# veils_v40.net
KiCad netlist of a schematic drawn in EAGLE
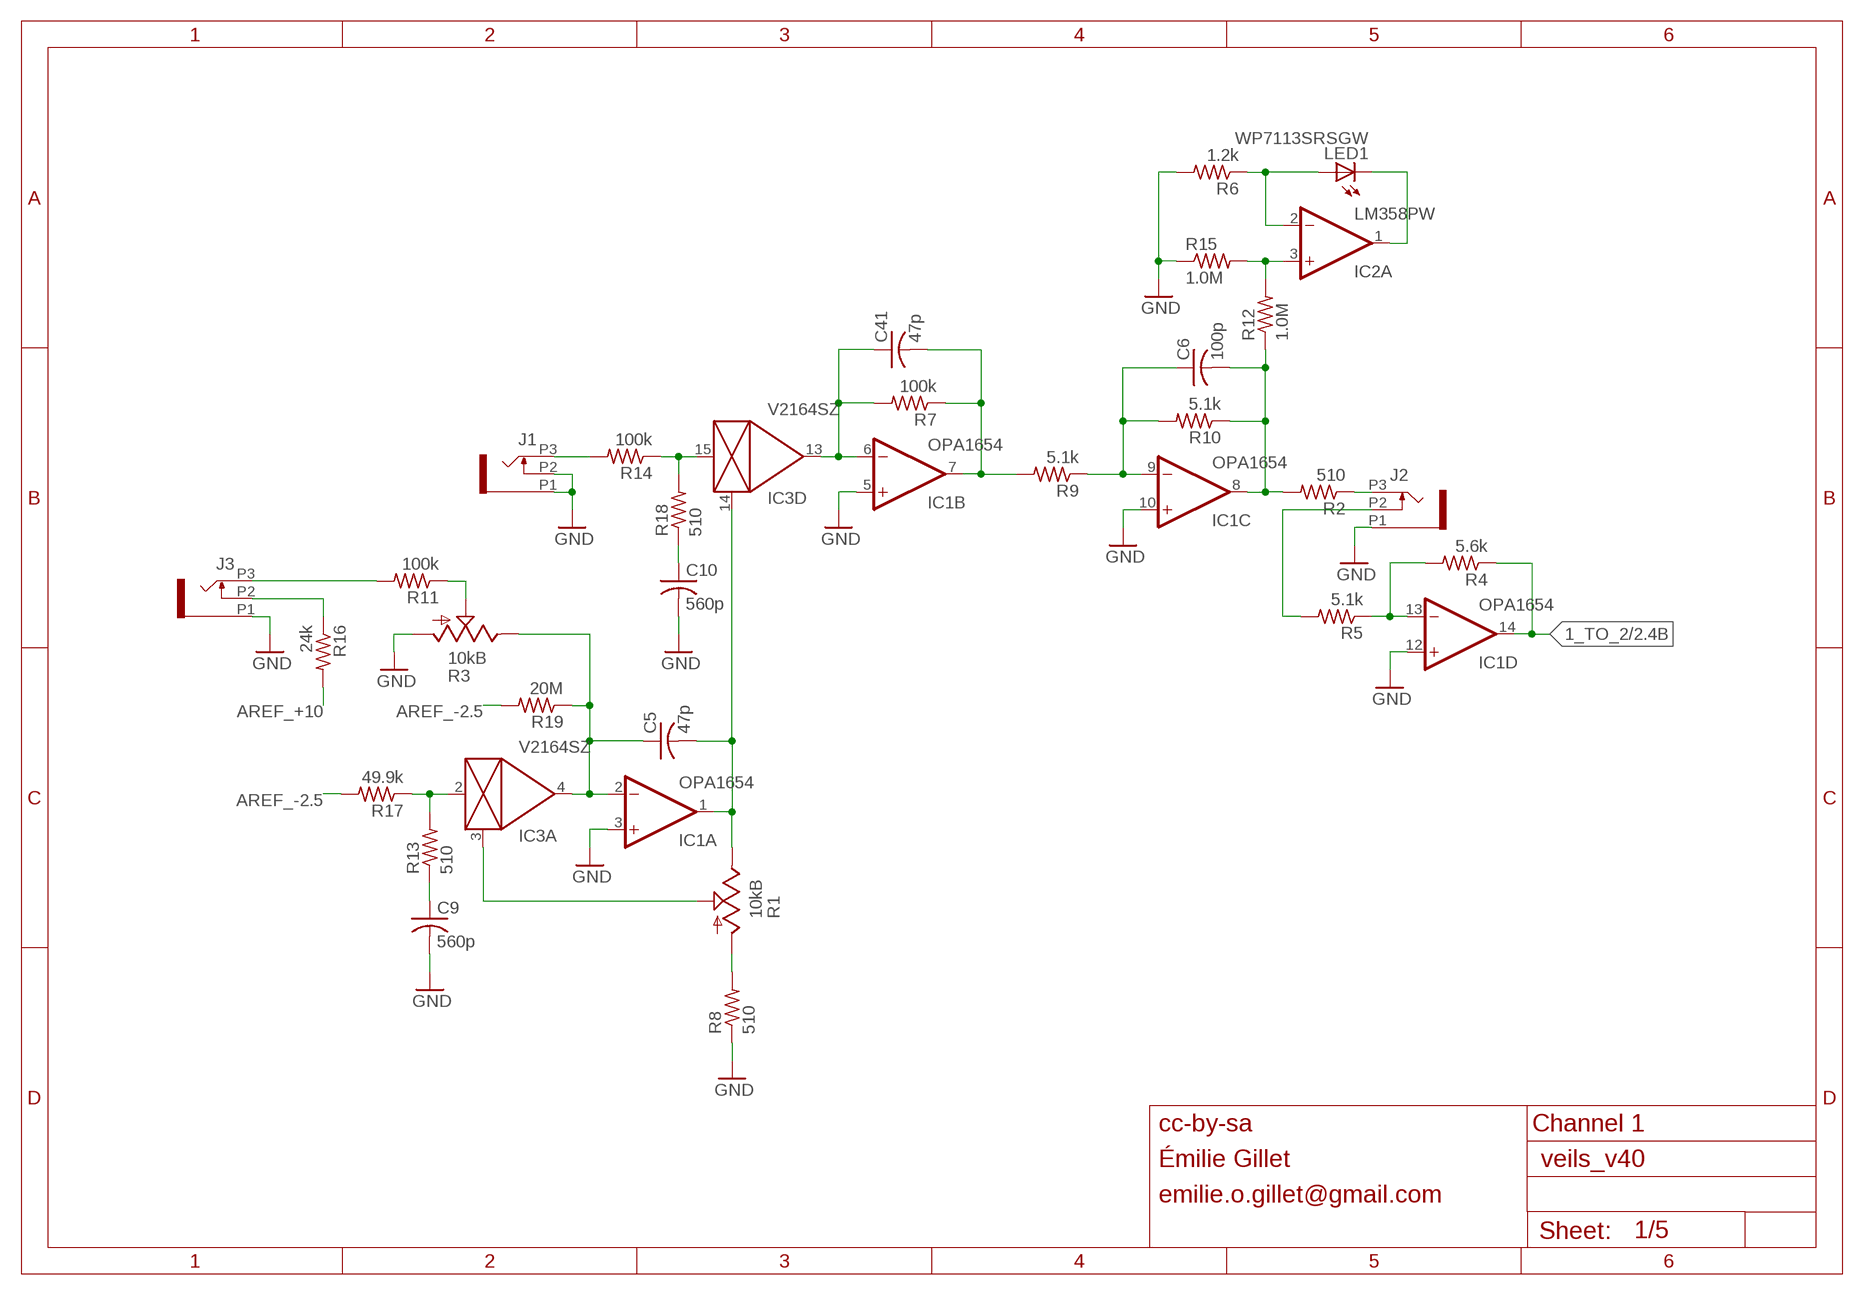
[diagram p0: schematic, sheet 1]
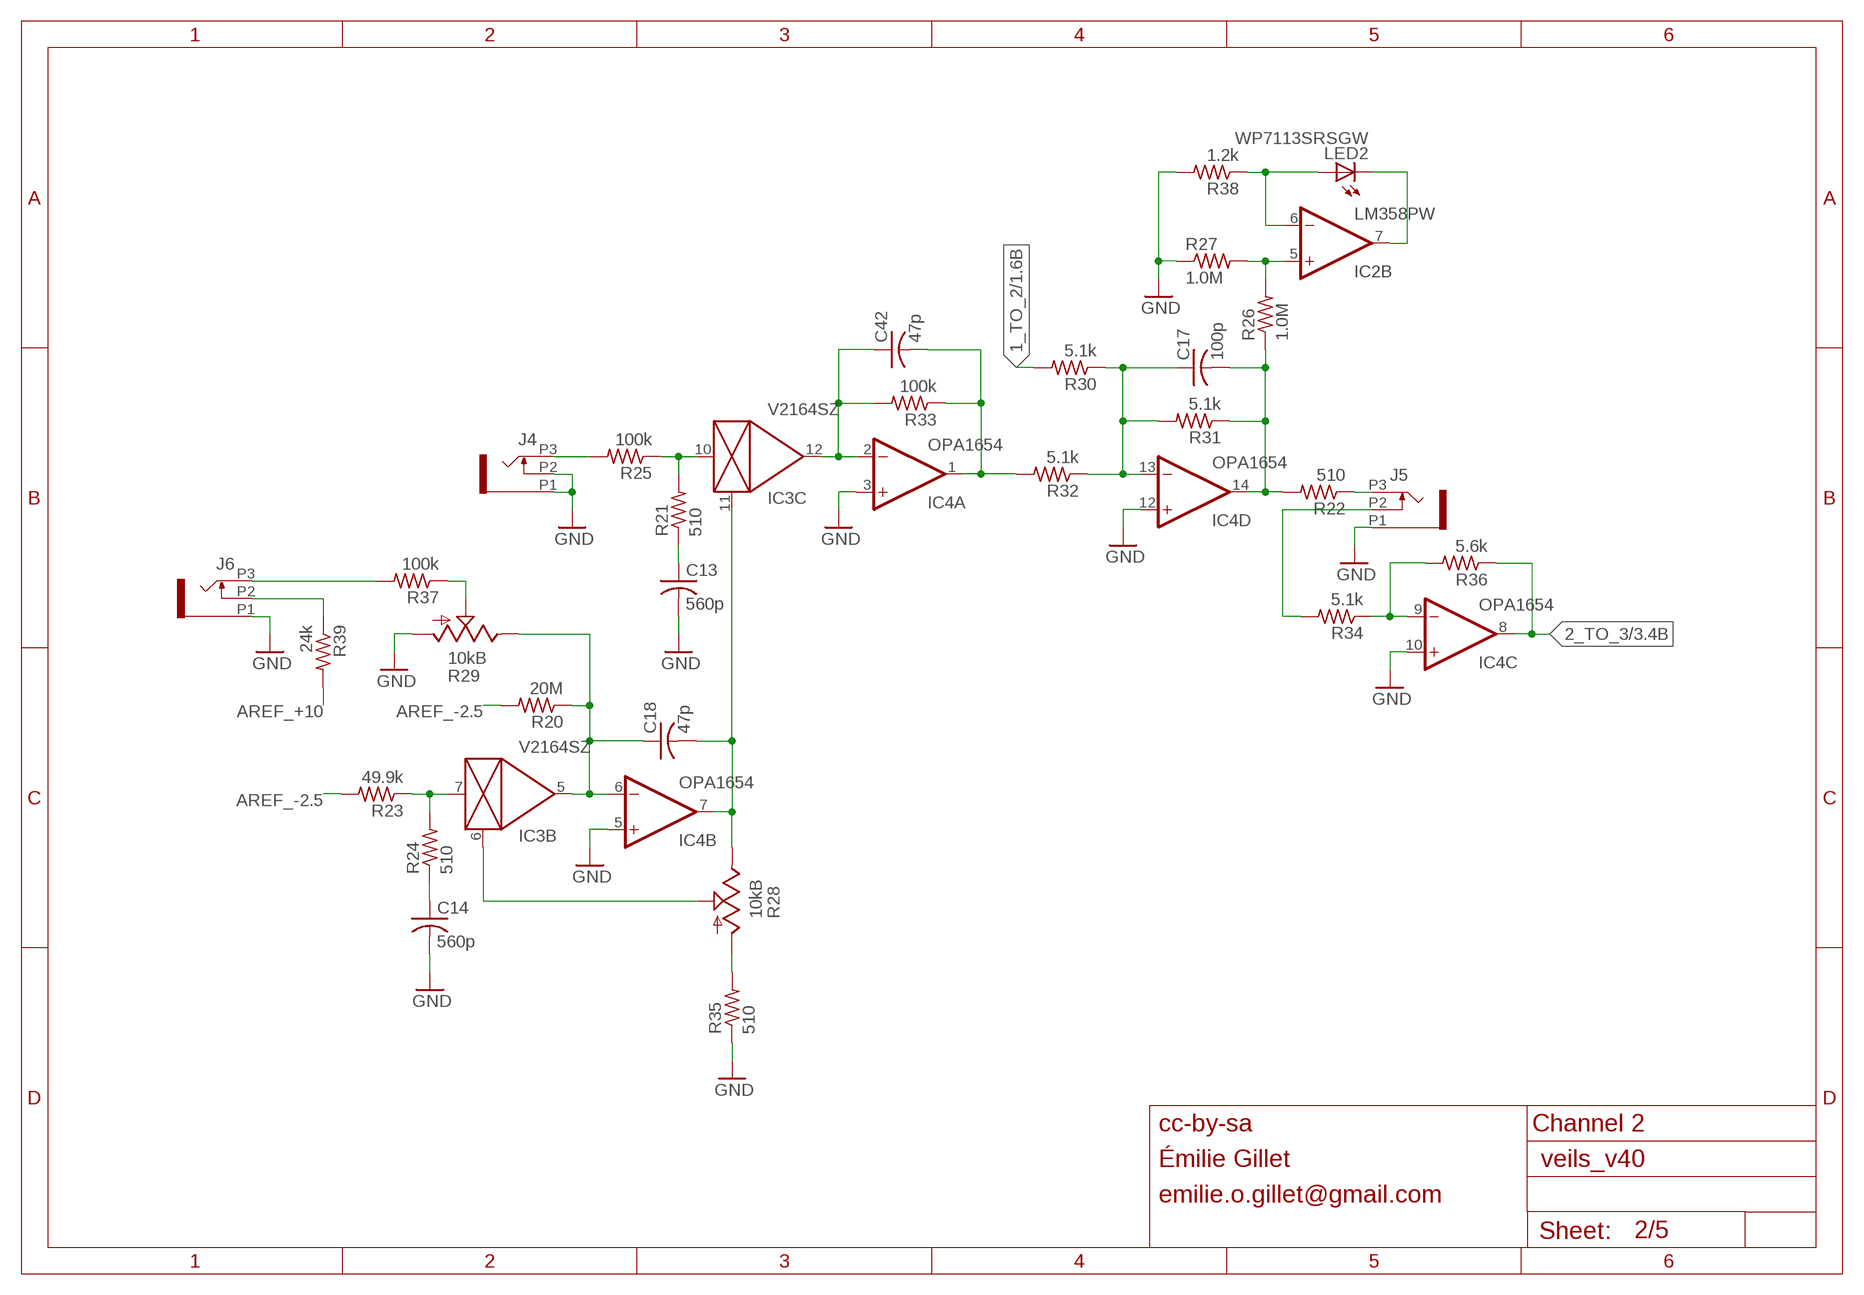
[diagram p1: schematic, sheet 2]
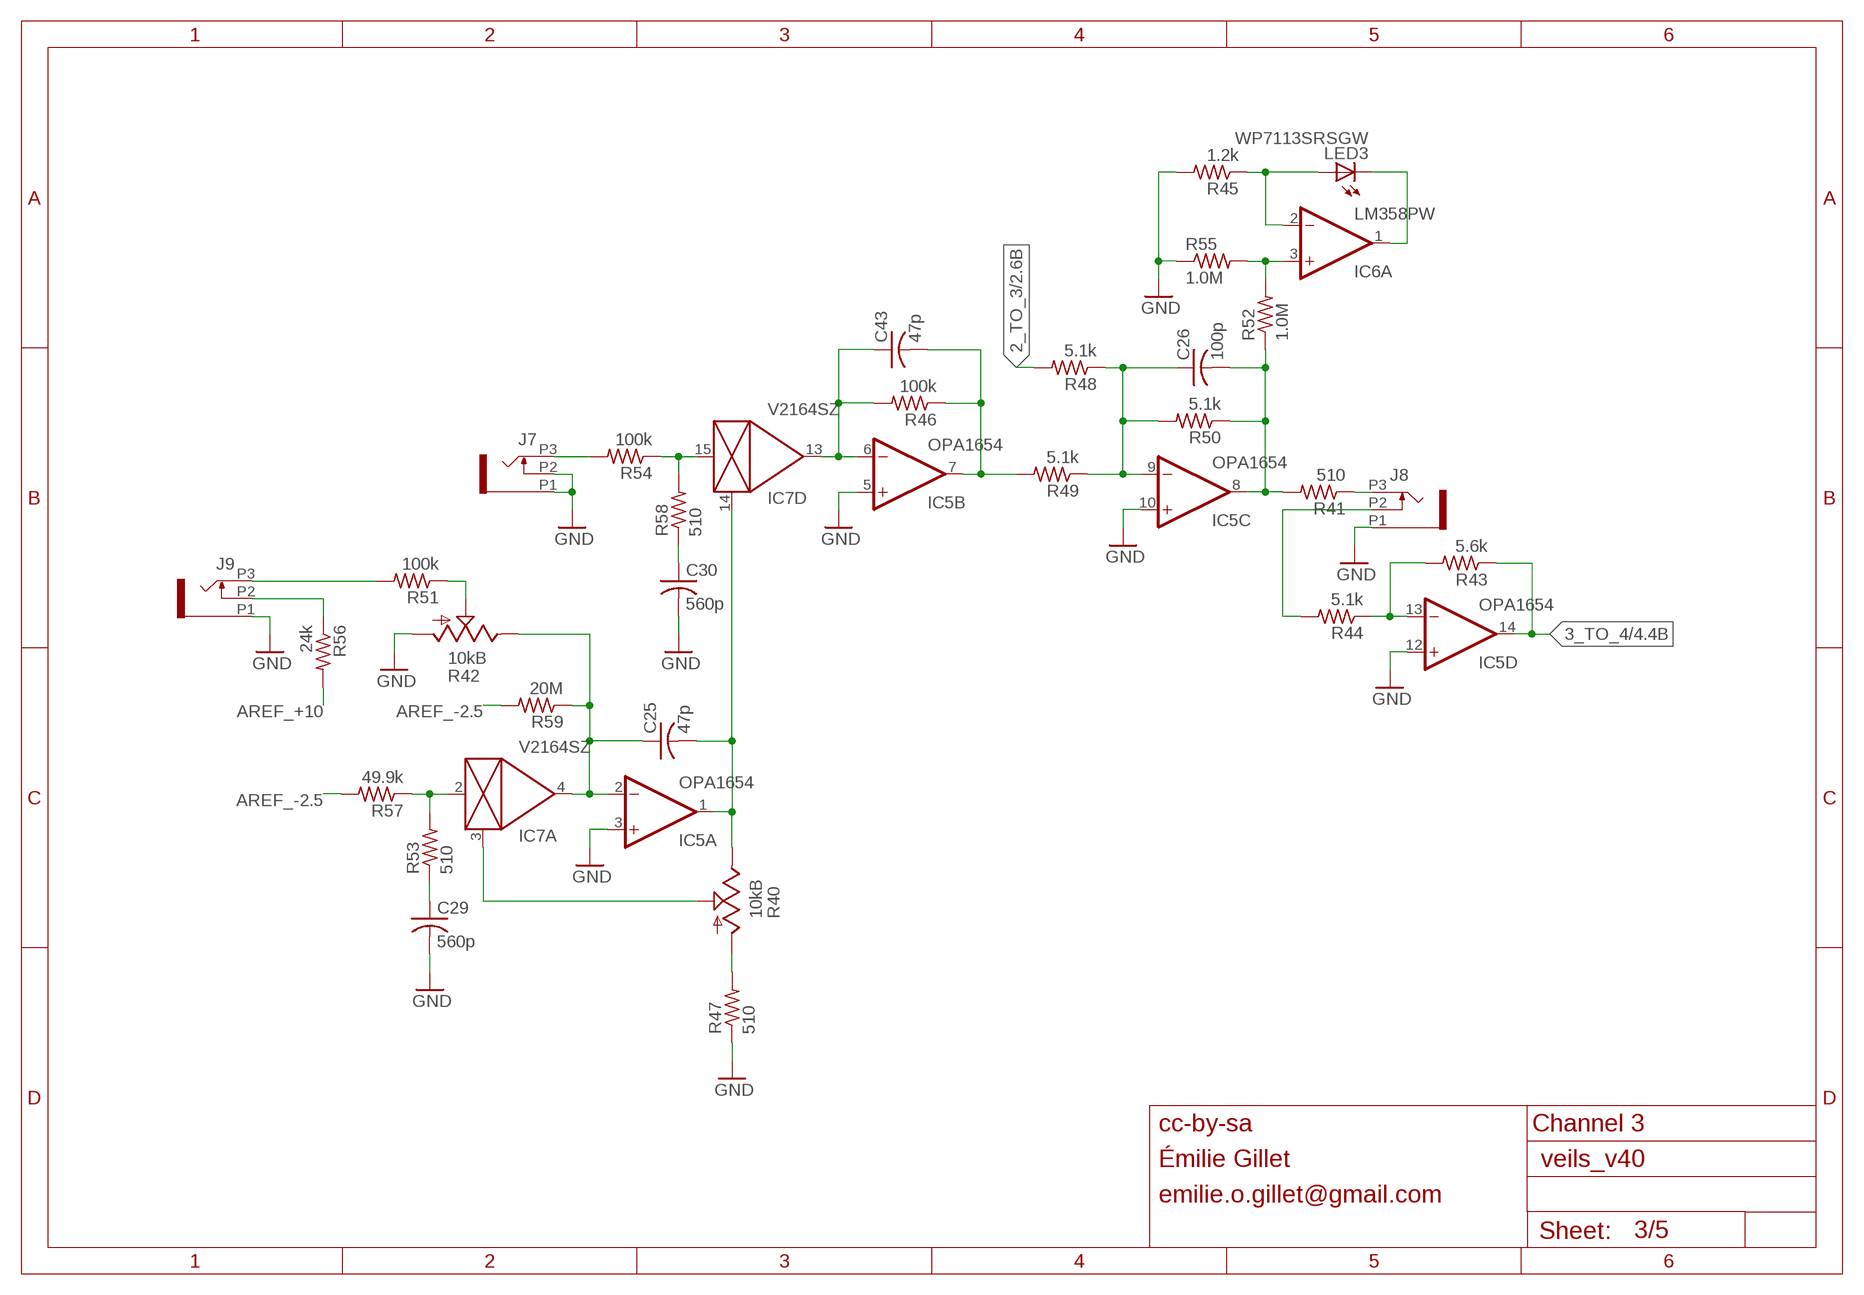
[diagram p2: schematic, sheet 3]
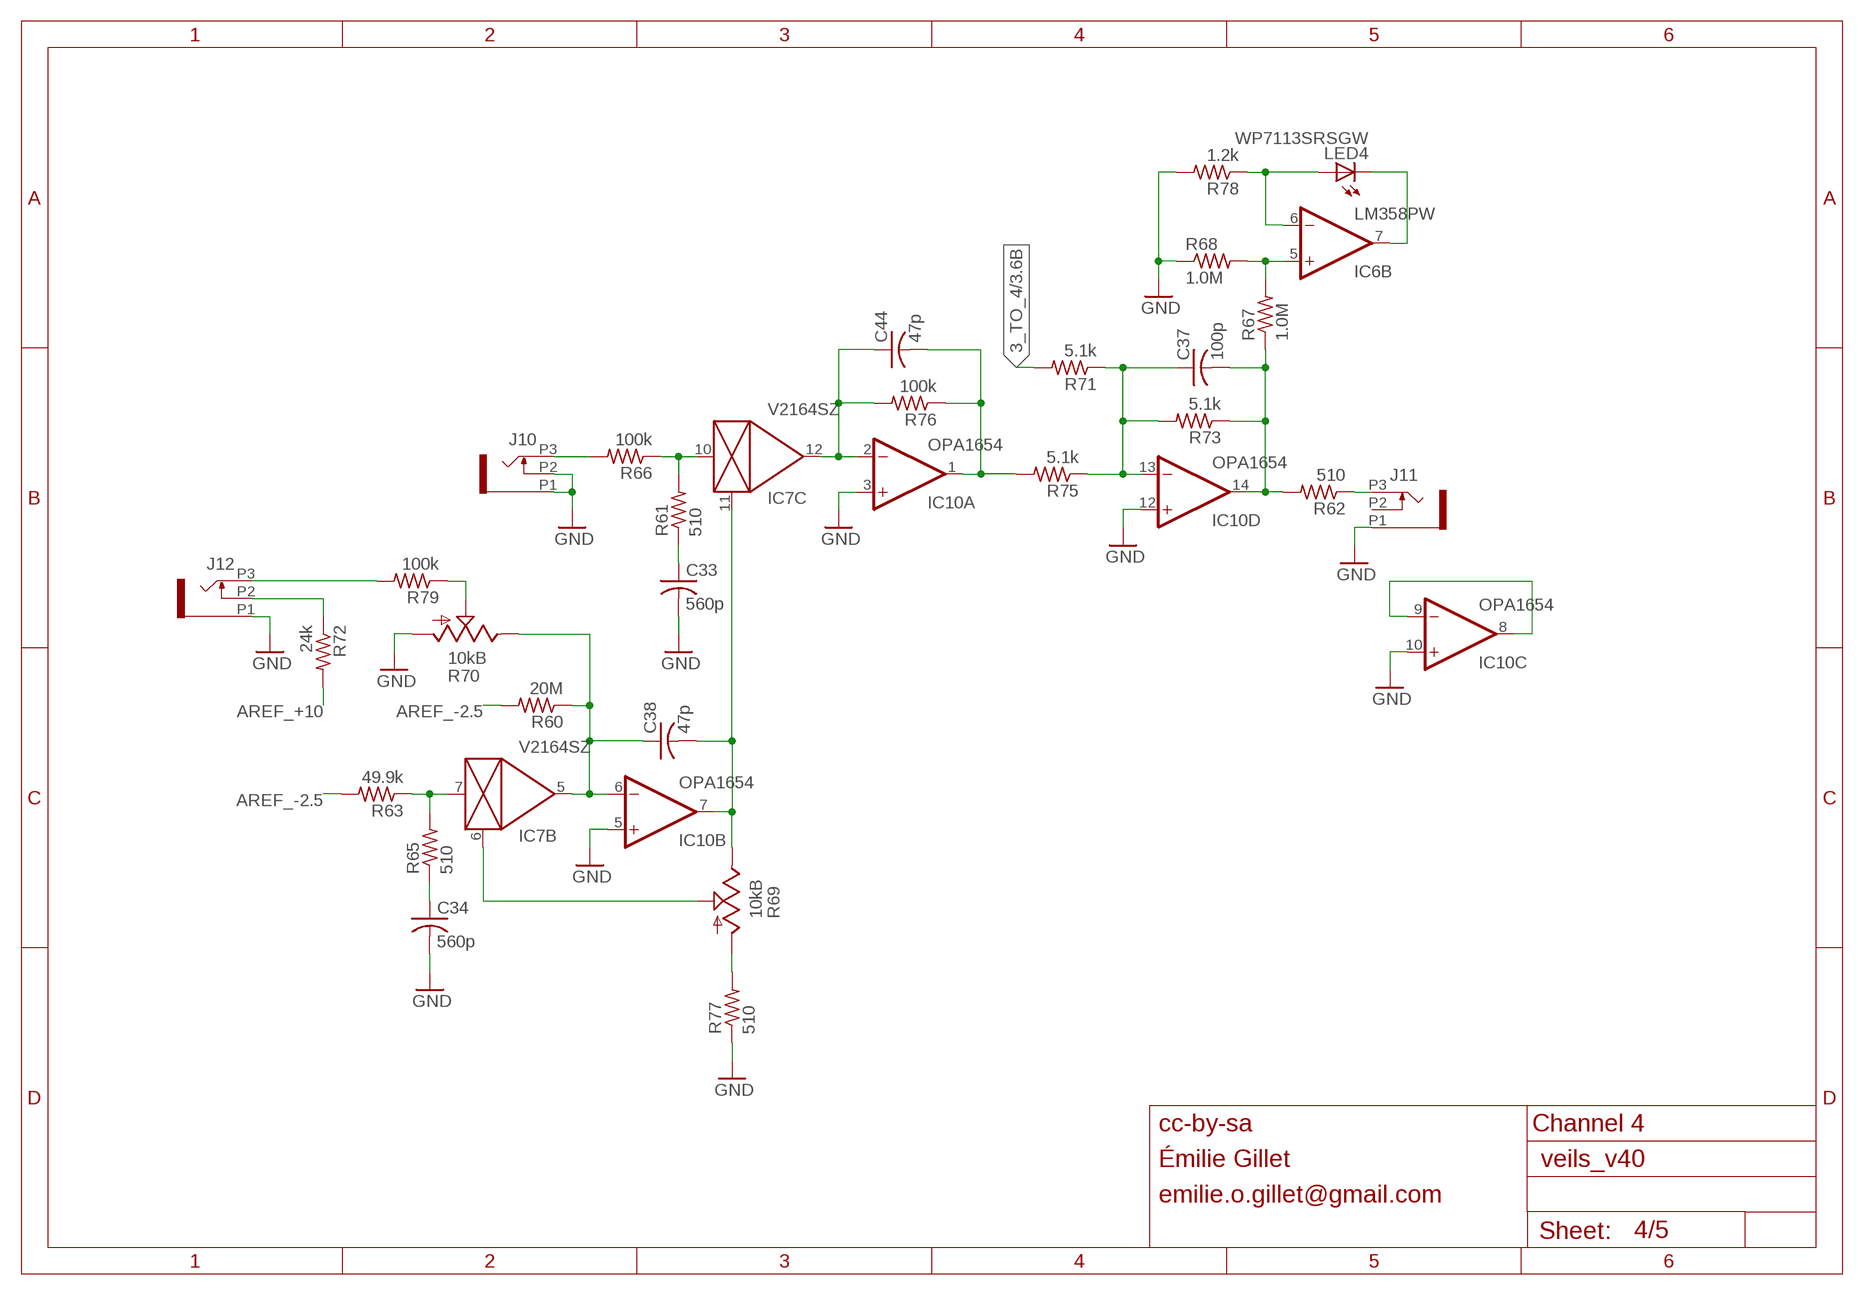
[diagram p3: schematic, sheet 4]
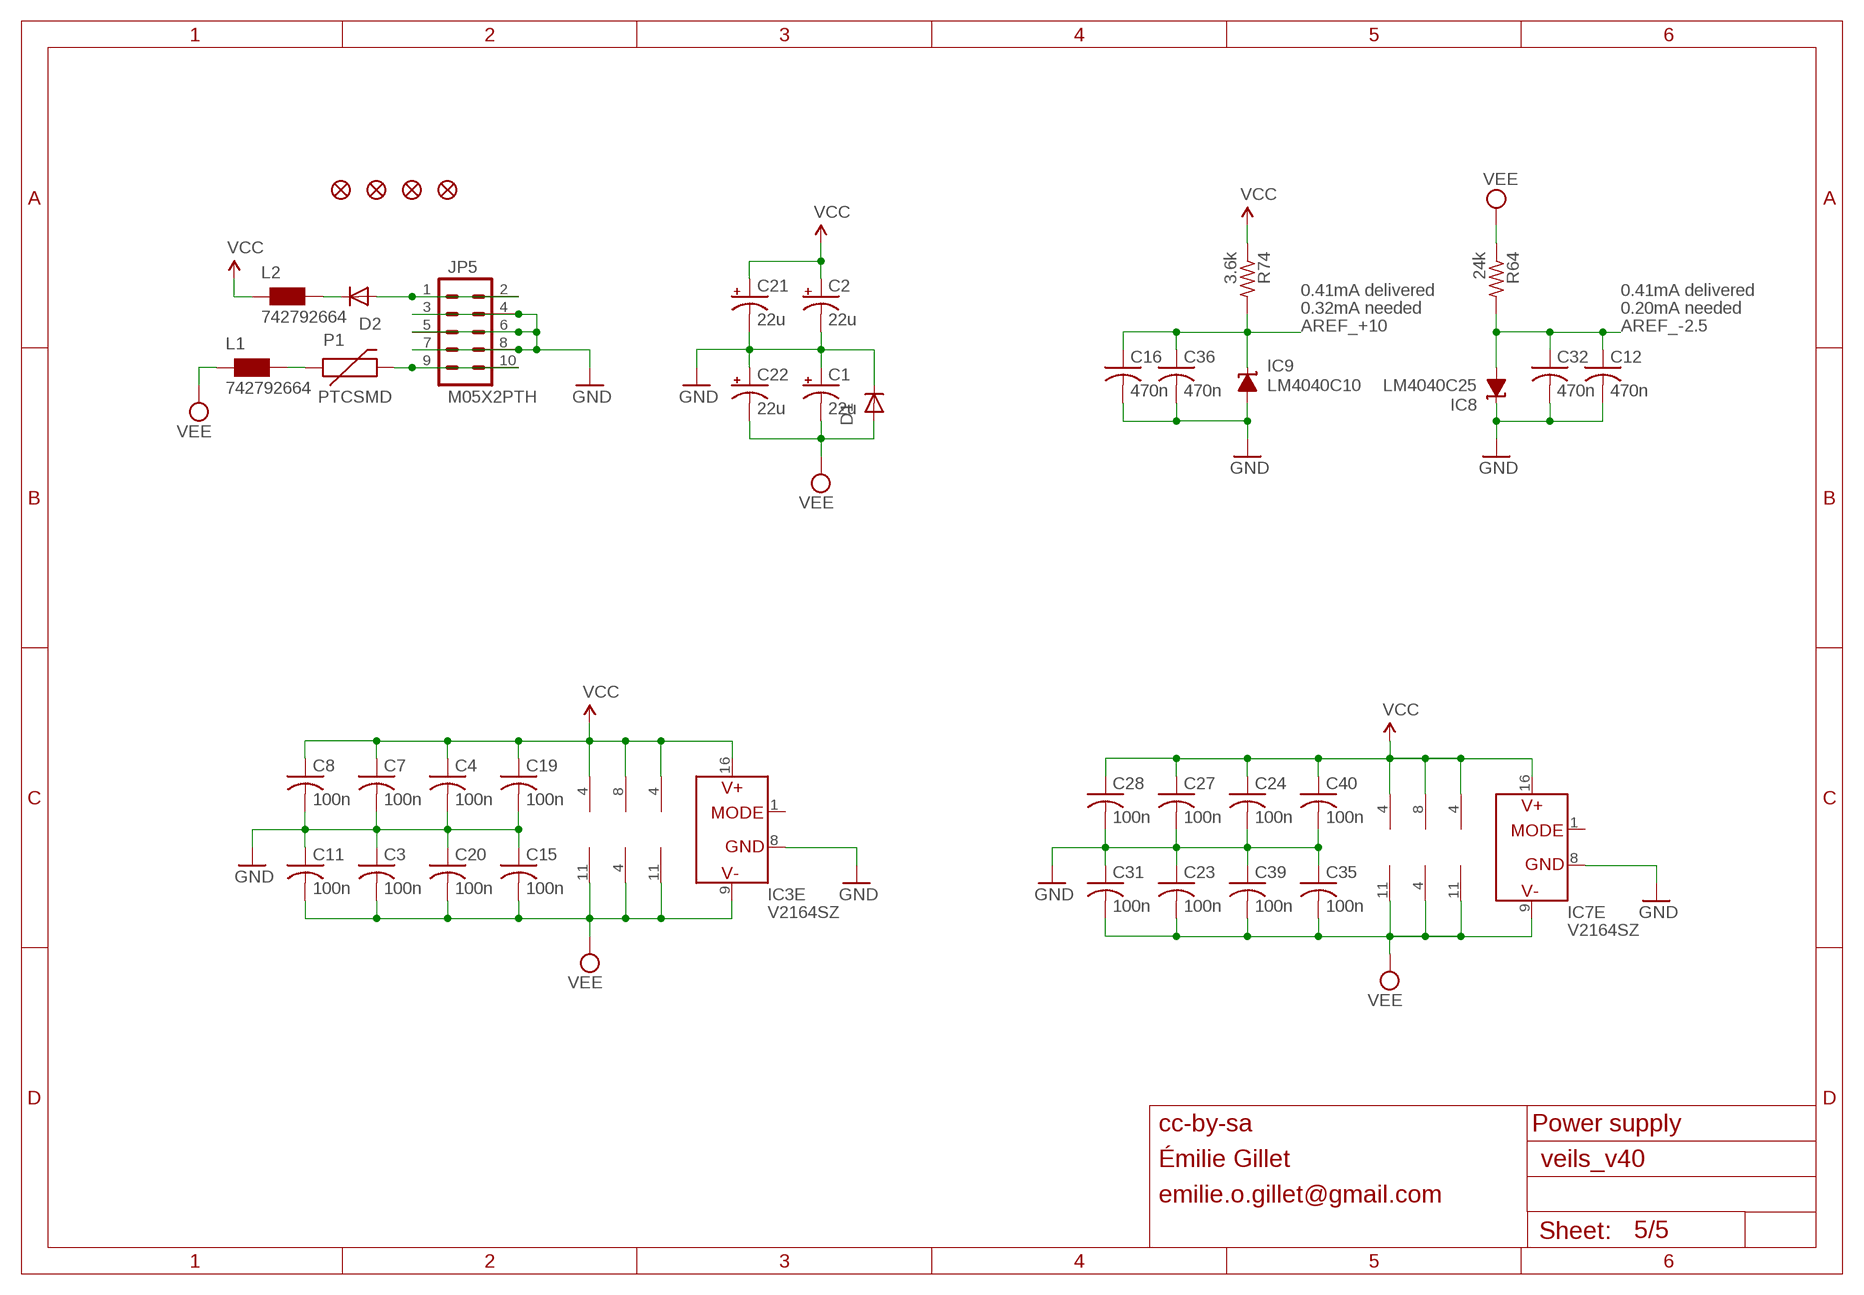
[diagram p4: schematic, sheet 5]

(export (version "E")
  (design (tool "Eeschema 10.0.6"))
  (components
    (comp (ref "C1")
      (value "22u")
      (footprint "eagle-import:PANASONIC_B")
      (libsource (lib "eagle-import") (part "CPOL-USB"))
    )
    (comp (ref "C2")
      (value "22u")
      (footprint "eagle-import:PANASONIC_B")
      (libsource (lib "eagle-import") (part "CPOL-USB"))
    )
    (comp (ref "C3")
      (value "100n")
      (footprint "eagle-import:C0402")
      (libsource (lib "eagle-import") (part "C-USC0402"))
    )
    (comp (ref "C4")
      (value "100n")
      (footprint "eagle-import:C0402")
      (libsource (lib "eagle-import") (part "C-USC0402"))
    )
    (comp (ref "C7")
      (value "100n")
      (footprint "eagle-import:C0402")
      (libsource (lib "eagle-import") (part "C-USC0402"))
    )
    (comp (ref "C8")
      (value "100n")
      (footprint "eagle-import:C0402")
      (libsource (lib "eagle-import") (part "C-USC0402"))
    )
    (comp (ref "C11")
      (value "100n")
      (footprint "eagle-import:C0402")
      (libsource (lib "eagle-import") (part "C-USC0402"))
    )
    (comp (ref "C12")
      (value "470n")
      (footprint "eagle-import:C0402")
      (libsource (lib "eagle-import") (part "C-USC0402"))
    )
    (comp (ref "C15")
      (value "100n")
      (footprint "eagle-import:C0402")
      (libsource (lib "eagle-import") (part "C-USC0402"))
    )
    (comp (ref "C16")
      (value "470n")
      (footprint "eagle-import:C0402")
      (libsource (lib "eagle-import") (part "C-USC0402"))
    )
    (comp (ref "C19")
      (value "100n")
      (footprint "eagle-import:C0402")
      (libsource (lib "eagle-import") (part "C-USC0402"))
    )
    (comp (ref "C20")
      (value "100n")
      (footprint "eagle-import:C0402")
      (libsource (lib "eagle-import") (part "C-USC0402"))
    )
    (comp (ref "C21")
      (value "22u")
      (footprint "eagle-import:PANASONIC_B")
      (libsource (lib "eagle-import") (part "CPOL-USB"))
    )
    (comp (ref "C22")
      (value "22u")
      (footprint "eagle-import:PANASONIC_B")
      (libsource (lib "eagle-import") (part "CPOL-USB"))
    )
    (comp (ref "C23")
      (value "100n")
      (footprint "eagle-import:C0402")
      (libsource (lib "eagle-import") (part "C-USC0402"))
    )
    (comp (ref "C24")
      (value "100n")
      (footprint "eagle-import:C0402")
      (libsource (lib "eagle-import") (part "C-USC0402"))
    )
    (comp (ref "C27")
      (value "100n")
      (footprint "eagle-import:C0402")
      (libsource (lib "eagle-import") (part "C-USC0402"))
    )
    (comp (ref "C28")
      (value "100n")
      (footprint "eagle-import:C0402")
      (libsource (lib "eagle-import") (part "C-USC0402"))
    )
    (comp (ref "C31")
      (value "100n")
      (footprint "eagle-import:C0402")
      (libsource (lib "eagle-import") (part "C-USC0402"))
    )
    (comp (ref "C32")
      (value "470n")
      (footprint "eagle-import:C0402")
      (libsource (lib "eagle-import") (part "C-USC0402"))
    )
    (comp (ref "C35")
      (value "100n")
      (footprint "eagle-import:C0402")
      (libsource (lib "eagle-import") (part "C-USC0402"))
    )
    (comp (ref "C36")
      (value "470n")
      (footprint "eagle-import:C0402")
      (libsource (lib "eagle-import") (part "C-USC0402"))
    )
    (comp (ref "C39")
      (value "100n")
      (footprint "eagle-import:C0402")
      (libsource (lib "eagle-import") (part "C-USC0402"))
    )
    (comp (ref "C40")
      (value "100n")
      (footprint "eagle-import:C0402")
      (libsource (lib "eagle-import") (part "C-USC0402"))
    )
    (comp (ref "D1")
      (value "1N5819HW")
      (footprint "eagle-import:SOD123")
      (libsource (lib "eagle-import") (part "DIODE-SOD123"))
    )
    (comp (ref "D2")
      (value "1N5819HW")
      (footprint "eagle-import:SOD123")
      (libsource (lib "eagle-import") (part "DIODE-SOD123"))
    )
    (comp (ref "IC1")
      (value "OPA1654")
      (footprint "eagle-import:TSSOP14")
      (libsource (lib "eagle-import") (part "TL074PW"))
    )
    (comp (ref "IC2")
      (value "LM358PW")
      (footprint "eagle-import:TSSOP8")
      (libsource (lib "eagle-import") (part "TL072PW"))
    )
    (comp (ref "IC3")
      (value "V2164SZ")
      (footprint "eagle-import:SOIC16N")
      (libsource (lib "eagle-import") (part "SSM2164S"))
    )
    (comp (ref "IC4")
      (value "OPA1654")
      (footprint "eagle-import:TSSOP14")
      (libsource (lib "eagle-import") (part "TL074PW"))
    )
    (comp (ref "IC5")
      (value "OPA1654")
      (footprint "eagle-import:TSSOP14")
      (libsource (lib "eagle-import") (part "TL074PW"))
    )
    (comp (ref "IC6")
      (value "LM358PW")
      (footprint "eagle-import:TSSOP8")
      (libsource (lib "eagle-import") (part "TL072PW"))
    )
    (comp (ref "IC7")
      (value "V2164SZ")
      (footprint "eagle-import:SOIC16N")
      (libsource (lib "eagle-import") (part "SSM2164S"))
    )
    (comp (ref "IC8")
      (value "LM4040C25")
      (footprint "eagle-import:DBZ_R-PDSO-G3")
      (libsource (lib "eagle-import") (part "LM4041DBZB12"))
    )
    (comp (ref "IC9")
      (value "LM4040C10")
      (footprint "eagle-import:DBZ_R-PDSO-G3")
      (libsource (lib "eagle-import") (part "LM4041DBZB12"))
    )
    (comp (ref "IC10")
      (value "OPA1654")
      (footprint "eagle-import:TSSOP14")
      (libsource (lib "eagle-import") (part "TL074PW"))
    )
    (comp (ref "JP1")
      (value "FIDUCIAL1X2")
      (footprint "eagle-import:FIDUCIAL-1X2")
      (libsource (lib "eagle-import") (part "FIDUCIAL1X2"))
    )
    (comp (ref "JP2")
      (value "FIDUCIAL1X2")
      (footprint "eagle-import:FIDUCIAL-1X2")
      (libsource (lib "eagle-import") (part "FIDUCIAL1X2"))
    )
    (comp (ref "JP3")
      (value "FIDUCIAL1X2")
      (footprint "eagle-import:FIDUCIAL-1X2")
      (libsource (lib "eagle-import") (part "FIDUCIAL1X2"))
    )
    (comp (ref "JP4")
      (value "FIDUCIAL1X2")
      (footprint "eagle-import:FIDUCIAL-1X2")
      (libsource (lib "eagle-import") (part "FIDUCIAL1X2"))
    )
    (comp (ref "JP5")
      (value "M05X2PTH")
      (footprint "eagle-import:AVR_ICSP")
      (libsource (lib "eagle-import") (part "M05X2PTH"))
    )
    (comp (ref "L1")
      (value "742792664")
      (footprint "eagle-import:0603")
      (libsource (lib "eagle-import") (part "WE-CBF_0603"))
    )
    (comp (ref "L2")
      (value "742792664")
      (footprint "eagle-import:0603")
      (libsource (lib "eagle-import") (part "WE-CBF_0603"))
    )
    (comp (ref "P1")
      (value "PTCSMD")
      (footprint "eagle-import:PTC-1206")
      (libsource (lib "eagle-import") (part "PTCSMD"))
    )
    (comp (ref "R64")
      (value "24k")
      (footprint "eagle-import:R0402")
      (libsource (lib "eagle-import") (part "R-US_R0402"))
    )
    (comp (ref "R74")
      (value "3.6k")
      (footprint "eagle-import:R0402")
      (libsource (lib "eagle-import") (part "R-US_R0402"))
    )
    (comp (ref "C13")
      (value "560p")
      (footprint "eagle-import:C0402")
      (libsource (lib "eagle-import") (part "C-USC0402"))
    )
    (comp (ref "C14")
      (value "560p")
      (footprint "eagle-import:C0402")
      (libsource (lib "eagle-import") (part "C-USC0402"))
    )
    (comp (ref "C17")
      (value "100p")
      (footprint "eagle-import:C0402")
      (libsource (lib "eagle-import") (part "C-USC0402"))
    )
    (comp (ref "C18")
      (value "47p")
      (footprint "eagle-import:C0402")
      (libsource (lib "eagle-import") (part "C-USC0402"))
    )
    (comp (ref "C42")
      (value "47p")
      (footprint "eagle-import:C0402")
      (libsource (lib "eagle-import") (part "C-USC0402"))
    )
    (comp (ref "J4")
      (value "PJ301_THONKICONN6")
      (footprint "eagle-import:WQP_PJ_301M6")
      (libsource (lib "eagle-import") (part "PJ301_THONKICONN6"))
    )
    (comp (ref "J5")
      (value "PJ301_THONKICONN6")
      (footprint "eagle-import:WQP_PJ_301M6")
      (libsource (lib "eagle-import") (part "PJ301_THONKICONN6"))
    )
    (comp (ref "J6")
      (value "PJ301_THONKICONN6")
      (footprint "eagle-import:WQP_PJ_301M6")
      (libsource (lib "eagle-import") (part "PJ301_THONKICONN6"))
    )
    (comp (ref "LED2")
      (value "WP7113SRSGW")
      (footprint "eagle-import:LED5MM")
      (libsource (lib "eagle-import") (part "LED5MM"))
    )
    (comp (ref "R20")
      (value "20M")
      (footprint "eagle-import:R0402")
      (libsource (lib "eagle-import") (part "R-US_R0402"))
    )
    (comp (ref "R21")
      (value "510")
      (footprint "eagle-import:R0402")
      (libsource (lib "eagle-import") (part "R-US_R0402"))
    )
    (comp (ref "R22")
      (value "510")
      (footprint "eagle-import:R0402")
      (libsource (lib "eagle-import") (part "R-US_R0402"))
    )
    (comp (ref "R23")
      (value "49.9k")
      (footprint "eagle-import:R0402")
      (libsource (lib "eagle-import") (part "R-US_R0402"))
    )
    (comp (ref "R24")
      (value "510")
      (footprint "eagle-import:R0402")
      (libsource (lib "eagle-import") (part "R-US_R0402"))
    )
    (comp (ref "R25")
      (value "100k")
      (footprint "eagle-import:R0402")
      (libsource (lib "eagle-import") (part "R-US_R0402"))
    )
    (comp (ref "R26")
      (value "1.0M")
      (footprint "eagle-import:R0402")
      (libsource (lib "eagle-import") (part "R-US_R0402"))
    )
    (comp (ref "R27")
      (value "1.0M")
      (footprint "eagle-import:R0402")
      (libsource (lib "eagle-import") (part "R-US_R0402"))
    )
    (comp (ref "R28")
      (value "10kB")
      (footprint "eagle-import:ALPS_POT_VERTICAL")
      (libsource (lib "eagle-import") (part "POT_USVERTICAL"))
    )
    (comp (ref "R29")
      (value "10kB")
      (footprint "eagle-import:ALPS_POT_VERTICAL_PS")
      (libsource (lib "eagle-import") (part "pot-alps_POT_USVERTICAL_PS"))
    )
    (comp (ref "R30")
      (value "5.1k")
      (footprint "eagle-import:R0402")
      (libsource (lib "eagle-import") (part "R-US_R0402"))
    )
    (comp (ref "R31")
      (value "5.1k")
      (footprint "eagle-import:R0402")
      (libsource (lib "eagle-import") (part "R-US_R0402"))
    )
    (comp (ref "R32")
      (value "5.1k")
      (footprint "eagle-import:R0402")
      (libsource (lib "eagle-import") (part "R-US_R0402"))
    )
    (comp (ref "R33")
      (value "100k")
      (footprint "eagle-import:R0402")
      (libsource (lib "eagle-import") (part "R-US_R0402"))
    )
    (comp (ref "R34")
      (value "5.1k")
      (footprint "eagle-import:R0402")
      (libsource (lib "eagle-import") (part "R-US_R0402"))
    )
    (comp (ref "R35")
      (value "510")
      (footprint "eagle-import:R0402")
      (libsource (lib "eagle-import") (part "R-US_R0402"))
    )
    (comp (ref "R36")
      (value "5.6k")
      (footprint "eagle-import:R0402")
      (libsource (lib "eagle-import") (part "R-US_R0402"))
    )
    (comp (ref "R37")
      (value "100k")
      (footprint "eagle-import:R0402")
      (libsource (lib "eagle-import") (part "R-US_R0402"))
    )
    (comp (ref "R38")
      (value "1.2k")
      (footprint "eagle-import:R0402")
      (libsource (lib "eagle-import") (part "R-US_R0402"))
    )
    (comp (ref "R39")
      (value "24k")
      (footprint "eagle-import:R0402")
      (libsource (lib "eagle-import") (part "R-US_R0402"))
    )
    (comp (ref "C33")
      (value "560p")
      (footprint "eagle-import:C0402")
      (libsource (lib "eagle-import") (part "C-USC0402"))
    )
    (comp (ref "C34")
      (value "560p")
      (footprint "eagle-import:C0402")
      (libsource (lib "eagle-import") (part "C-USC0402"))
    )
    (comp (ref "C37")
      (value "100p")
      (footprint "eagle-import:C0402")
      (libsource (lib "eagle-import") (part "C-USC0402"))
    )
    (comp (ref "C38")
      (value "47p")
      (footprint "eagle-import:C0402")
      (libsource (lib "eagle-import") (part "C-USC0402"))
    )
    (comp (ref "C44")
      (value "47p")
      (footprint "eagle-import:C0402")
      (libsource (lib "eagle-import") (part "C-USC0402"))
    )
    (comp (ref "J10")
      (value "PJ301_THONKICONN6")
      (footprint "eagle-import:WQP_PJ_301M6")
      (libsource (lib "eagle-import") (part "PJ301_THONKICONN6"))
    )
    (comp (ref "J11")
      (value "PJ301_THONKICONN6")
      (footprint "eagle-import:WQP_PJ_301M6")
      (libsource (lib "eagle-import") (part "PJ301_THONKICONN6"))
    )
    (comp (ref "J12")
      (value "PJ301_THONKICONN6")
      (footprint "eagle-import:WQP_PJ_301M6")
      (libsource (lib "eagle-import") (part "PJ301_THONKICONN6"))
    )
    (comp (ref "LED4")
      (value "WP7113SRSGW")
      (footprint "eagle-import:LED5MM")
      (libsource (lib "eagle-import") (part "LED5MM"))
    )
    (comp (ref "R60")
      (value "20M")
      (footprint "eagle-import:R0402")
      (libsource (lib "eagle-import") (part "R-US_R0402"))
    )
    (comp (ref "R61")
      (value "510")
      (footprint "eagle-import:R0402")
      (libsource (lib "eagle-import") (part "R-US_R0402"))
    )
    (comp (ref "R62")
      (value "510")
      (footprint "eagle-import:R0402")
      (libsource (lib "eagle-import") (part "R-US_R0402"))
    )
    (comp (ref "R63")
      (value "49.9k")
      (footprint "eagle-import:R0402")
      (libsource (lib "eagle-import") (part "R-US_R0402"))
    )
    (comp (ref "R65")
      (value "510")
      (footprint "eagle-import:R0402")
      (libsource (lib "eagle-import") (part "R-US_R0402"))
    )
    (comp (ref "R66")
      (value "100k")
      (footprint "eagle-import:R0402")
      (libsource (lib "eagle-import") (part "R-US_R0402"))
    )
    (comp (ref "R67")
      (value "1.0M")
      (footprint "eagle-import:R0402")
      (libsource (lib "eagle-import") (part "R-US_R0402"))
    )
    (comp (ref "R68")
      (value "1.0M")
      (footprint "eagle-import:R0402")
      (libsource (lib "eagle-import") (part "R-US_R0402"))
    )
    (comp (ref "R69")
      (value "10kB")
      (footprint "eagle-import:ALPS_POT_VERTICAL")
      (libsource (lib "eagle-import") (part "POT_USVERTICAL"))
    )
    (comp (ref "R70")
      (value "10kB")
      (footprint "eagle-import:ALPS_POT_VERTICAL_PS")
      (libsource (lib "eagle-import") (part "pot-alps_POT_USVERTICAL_PS"))
    )
    (comp (ref "R71")
      (value "5.1k")
      (footprint "eagle-import:R0402")
      (libsource (lib "eagle-import") (part "R-US_R0402"))
    )
    (comp (ref "R72")
      (value "24k")
      (footprint "eagle-import:R0402")
      (libsource (lib "eagle-import") (part "R-US_R0402"))
    )
    (comp (ref "R73")
      (value "5.1k")
      (footprint "eagle-import:R0402")
      (libsource (lib "eagle-import") (part "R-US_R0402"))
    )
    (comp (ref "R75")
      (value "5.1k")
      (footprint "eagle-import:R0402")
      (libsource (lib "eagle-import") (part "R-US_R0402"))
    )
    (comp (ref "R76")
      (value "100k")
      (footprint "eagle-import:R0402")
      (libsource (lib "eagle-import") (part "R-US_R0402"))
    )
    (comp (ref "R77")
      (value "510")
      (footprint "eagle-import:R0402")
      (libsource (lib "eagle-import") (part "R-US_R0402"))
    )
    (comp (ref "R78")
      (value "1.2k")
      (footprint "eagle-import:R0402")
      (libsource (lib "eagle-import") (part "R-US_R0402"))
    )
    (comp (ref "R79")
      (value "100k")
      (footprint "eagle-import:R0402")
      (libsource (lib "eagle-import") (part "R-US_R0402"))
    )
    (comp (ref "C25")
      (value "47p")
      (footprint "eagle-import:C0402")
      (libsource (lib "eagle-import") (part "C-USC0402"))
    )
    (comp (ref "C26")
      (value "100p")
      (footprint "eagle-import:C0402")
      (libsource (lib "eagle-import") (part "C-USC0402"))
    )
    (comp (ref "C29")
      (value "560p")
      (footprint "eagle-import:C0402")
      (libsource (lib "eagle-import") (part "C-USC0402"))
    )
    (comp (ref "C30")
      (value "560p")
      (footprint "eagle-import:C0402")
      (libsource (lib "eagle-import") (part "C-USC0402"))
    )
    (comp (ref "C43")
      (value "47p")
      (footprint "eagle-import:C0402")
      (libsource (lib "eagle-import") (part "C-USC0402"))
    )
    (comp (ref "J7")
      (value "PJ301_THONKICONN6")
      (footprint "eagle-import:WQP_PJ_301M6")
      (libsource (lib "eagle-import") (part "PJ301_THONKICONN6"))
    )
    (comp (ref "J8")
      (value "PJ301_THONKICONN6")
      (footprint "eagle-import:WQP_PJ_301M6")
      (libsource (lib "eagle-import") (part "PJ301_THONKICONN6"))
    )
    (comp (ref "J9")
      (value "PJ301_THONKICONN6")
      (footprint "eagle-import:WQP_PJ_301M6")
      (libsource (lib "eagle-import") (part "PJ301_THONKICONN6"))
    )
    (comp (ref "LED3")
      (value "WP7113SRSGW")
      (footprint "eagle-import:LED5MM")
      (libsource (lib "eagle-import") (part "LED5MM"))
    )
    (comp (ref "R40")
      (value "10kB")
      (footprint "eagle-import:ALPS_POT_VERTICAL")
      (libsource (lib "eagle-import") (part "POT_USVERTICAL"))
    )
    (comp (ref "R41")
      (value "510")
      (footprint "eagle-import:R0402")
      (libsource (lib "eagle-import") (part "R-US_R0402"))
    )
    (comp (ref "R42")
      (value "10kB")
      (footprint "eagle-import:ALPS_POT_VERTICAL_PS")
      (libsource (lib "eagle-import") (part "pot-alps_POT_USVERTICAL_PS"))
    )
    (comp (ref "R43")
      (value "5.6k")
      (footprint "eagle-import:R0402")
      (libsource (lib "eagle-import") (part "R-US_R0402"))
    )
    (comp (ref "R44")
      (value "5.1k")
      (footprint "eagle-import:R0402")
      (libsource (lib "eagle-import") (part "R-US_R0402"))
    )
    (comp (ref "R45")
      (value "1.2k")
      (footprint "eagle-import:R0402")
      (libsource (lib "eagle-import") (part "R-US_R0402"))
    )
    (comp (ref "R46")
      (value "100k")
      (footprint "eagle-import:R0402")
      (libsource (lib "eagle-import") (part "R-US_R0402"))
    )
    (comp (ref "R47")
      (value "510")
      (footprint "eagle-import:R0402")
      (libsource (lib "eagle-import") (part "R-US_R0402"))
    )
    (comp (ref "R48")
      (value "5.1k")
      (footprint "eagle-import:R0402")
      (libsource (lib "eagle-import") (part "R-US_R0402"))
    )
    (comp (ref "R49")
      (value "5.1k")
      (footprint "eagle-import:R0402")
      (libsource (lib "eagle-import") (part "R-US_R0402"))
    )
    (comp (ref "R50")
      (value "5.1k")
      (footprint "eagle-import:R0402")
      (libsource (lib "eagle-import") (part "R-US_R0402"))
    )
    (comp (ref "R51")
      (value "100k")
      (footprint "eagle-import:R0402")
      (libsource (lib "eagle-import") (part "R-US_R0402"))
    )
    (comp (ref "R52")
      (value "1.0M")
      (footprint "eagle-import:R0402")
      (libsource (lib "eagle-import") (part "R-US_R0402"))
    )
    (comp (ref "R53")
      (value "510")
      (footprint "eagle-import:R0402")
      (libsource (lib "eagle-import") (part "R-US_R0402"))
    )
    (comp (ref "R54")
      (value "100k")
      (footprint "eagle-import:R0402")
      (libsource (lib "eagle-import") (part "R-US_R0402"))
    )
    (comp (ref "R55")
      (value "1.0M")
      (footprint "eagle-import:R0402")
      (libsource (lib "eagle-import") (part "R-US_R0402"))
    )
    (comp (ref "R56")
      (value "24k")
      (footprint "eagle-import:R0402")
      (libsource (lib "eagle-import") (part "R-US_R0402"))
    )
    (comp (ref "R57")
      (value "49.9k")
      (footprint "eagle-import:R0402")
      (libsource (lib "eagle-import") (part "R-US_R0402"))
    )
    (comp (ref "R58")
      (value "510")
      (footprint "eagle-import:R0402")
      (libsource (lib "eagle-import") (part "R-US_R0402"))
    )
    (comp (ref "R59")
      (value "20M")
      (footprint "eagle-import:R0402")
      (libsource (lib "eagle-import") (part "R-US_R0402"))
    )
    (comp (ref "C5")
      (value "47p")
      (footprint "eagle-import:C0402")
      (libsource (lib "eagle-import") (part "C-USC0402"))
    )
    (comp (ref "C6")
      (value "100p")
      (footprint "eagle-import:C0402")
      (libsource (lib "eagle-import") (part "C-USC0402"))
    )
    (comp (ref "C9")
      (value "560p")
      (footprint "eagle-import:C0402")
      (libsource (lib "eagle-import") (part "C-USC0402"))
    )
    (comp (ref "C10")
      (value "560p")
      (footprint "eagle-import:C0402")
      (libsource (lib "eagle-import") (part "C-USC0402"))
    )
    (comp (ref "C41")
      (value "47p")
      (footprint "eagle-import:C0402")
      (libsource (lib "eagle-import") (part "C-USC0402"))
    )
    (comp (ref "J1")
      (value "PJ301_THONKICONN6")
      (footprint "eagle-import:WQP_PJ_301M6")
      (libsource (lib "eagle-import") (part "PJ301_THONKICONN6"))
    )
    (comp (ref "J2")
      (value "PJ301_THONKICONN6")
      (footprint "eagle-import:WQP_PJ_301M6")
      (libsource (lib "eagle-import") (part "PJ301_THONKICONN6"))
    )
    (comp (ref "J3")
      (value "PJ301_THONKICONN6")
      (footprint "eagle-import:WQP_PJ_301M6")
      (libsource (lib "eagle-import") (part "PJ301_THONKICONN6"))
    )
    (comp (ref "LED1")
      (value "WP7113SRSGW")
      (footprint "eagle-import:LED5MM")
      (libsource (lib "eagle-import") (part "LED5MM"))
    )
    (comp (ref "R1")
      (value "10kB")
      (footprint "eagle-import:ALPS_POT_VERTICAL")
      (libsource (lib "eagle-import") (part "POT_USVERTICAL"))
    )
    (comp (ref "R2")
      (value "510")
      (footprint "eagle-import:R0402")
      (libsource (lib "eagle-import") (part "R-US_R0402"))
    )
    (comp (ref "R3")
      (value "10kB")
      (footprint "eagle-import:ALPS_POT_VERTICAL_PS")
      (libsource (lib "eagle-import") (part "pot-alps_POT_USVERTICAL_PS"))
    )
    (comp (ref "R4")
      (value "5.6k")
      (footprint "eagle-import:R0402")
      (libsource (lib "eagle-import") (part "R-US_R0402"))
    )
    (comp (ref "R5")
      (value "5.1k")
      (footprint "eagle-import:R0402")
      (libsource (lib "eagle-import") (part "R-US_R0402"))
    )
    (comp (ref "R6")
      (value "1.2k")
      (footprint "eagle-import:R0402")
      (libsource (lib "eagle-import") (part "R-US_R0402"))
    )
    (comp (ref "R7")
      (value "100k")
      (footprint "eagle-import:R0402")
      (libsource (lib "eagle-import") (part "R-US_R0402"))
    )
    (comp (ref "R8")
      (value "510")
      (footprint "eagle-import:R0402")
      (libsource (lib "eagle-import") (part "R-US_R0402"))
    )
    (comp (ref "R9")
      (value "5.1k")
      (footprint "eagle-import:R0402")
      (libsource (lib "eagle-import") (part "R-US_R0402"))
    )
    (comp (ref "R10")
      (value "5.1k")
      (footprint "eagle-import:R0402")
      (libsource (lib "eagle-import") (part "R-US_R0402"))
    )
    (comp (ref "R11")
      (value "100k")
      (footprint "eagle-import:R0402")
      (libsource (lib "eagle-import") (part "R-US_R0402"))
    )
    (comp (ref "R12")
      (value "1.0M")
      (footprint "eagle-import:R0402")
      (libsource (lib "eagle-import") (part "R-US_R0402"))
    )
    (comp (ref "R13")
      (value "510")
      (footprint "eagle-import:R0402")
      (libsource (lib "eagle-import") (part "R-US_R0402"))
    )
    (comp (ref "R14")
      (value "100k")
      (footprint "eagle-import:R0402")
      (libsource (lib "eagle-import") (part "R-US_R0402"))
    )
    (comp (ref "R15")
      (value "1.0M")
      (footprint "eagle-import:R0402")
      (libsource (lib "eagle-import") (part "R-US_R0402"))
    )
    (comp (ref "R16")
      (value "24k")
      (footprint "eagle-import:R0402")
      (libsource (lib "eagle-import") (part "R-US_R0402"))
    )
    (comp (ref "R17")
      (value "49.9k")
      (footprint "eagle-import:R0402")
      (libsource (lib "eagle-import") (part "R-US_R0402"))
    )
    (comp (ref "R18")
      (value "510")
      (footprint "eagle-import:R0402")
      (libsource (lib "eagle-import") (part "R-US_R0402"))
    )
    (comp (ref "R19")
      (value "20M")
      (footprint "eagle-import:R0402")
      (libsource (lib "eagle-import") (part "R-US_R0402"))
    )
  )
  (nets
    (net (code "1") (name "1_TO_2") (class "Default")
      (node (ref "IC1") (pin "14") (pinfunction "OUT_14") (pintype "output"))
      (node (ref "R30") (pin "2") (pinfunction "2_2") (pintype "passive"))
      (node (ref "R4") (pin "1") (pinfunction "1_1") (pintype "passive"))
    )
    (net (code "2") (name "2_TO_3") (class "Default")
      (node (ref "IC4") (pin "8") (pinfunction "OUT_8") (pintype "output"))
      (node (ref "R36") (pin "1") (pinfunction "1_1") (pintype "passive"))
      (node (ref "R48") (pin "2") (pinfunction "2_2") (pintype "passive"))
    )
    (net (code "3") (name "3_TO_4") (class "Default")
      (node (ref "IC5") (pin "14") (pinfunction "OUT_14") (pintype "output"))
      (node (ref "R43") (pin "1") (pinfunction "1_1") (pintype "passive"))
      (node (ref "R71") (pin "2") (pinfunction "2_2") (pintype "passive"))
    )
    (net (code "4") (name "AREF_+10") (class "Default")
      (node (ref "C16") (pin "1") (pinfunction "1_1") (pintype "passive"))
      (node (ref "C36") (pin "1") (pinfunction "1_1") (pintype "passive"))
      (node (ref "IC9") (pin "1") (pinfunction "C_1") (pintype "passive"))
      (node (ref "R16") (pin "2") (pinfunction "2_2") (pintype "passive"))
      (node (ref "R39") (pin "2") (pinfunction "2_2") (pintype "passive"))
      (node (ref "R56") (pin "2") (pinfunction "2_2") (pintype "passive"))
      (node (ref "R72") (pin "2") (pinfunction "2_2") (pintype "passive"))
      (node (ref "R74") (pin "2") (pinfunction "2_2") (pintype "passive"))
    )
    (net (code "5") (name "AREF_-2.5") (class "Default")
      (node (ref "C12") (pin "1") (pinfunction "1_1") (pintype "passive"))
      (node (ref "C32") (pin "1") (pinfunction "1_1") (pintype "passive"))
      (node (ref "IC8") (pin "2") (pinfunction "A_2") (pintype "passive"))
      (node (ref "R17") (pin "2") (pinfunction "2_2") (pintype "passive"))
      (node (ref "R19") (pin "2") (pinfunction "2_2") (pintype "passive"))
      (node (ref "R20") (pin "2") (pinfunction "2_2") (pintype "passive"))
      (node (ref "R23") (pin "2") (pinfunction "2_2") (pintype "passive"))
      (node (ref "R57") (pin "2") (pinfunction "2_2") (pintype "passive"))
      (node (ref "R59") (pin "2") (pinfunction "2_2") (pintype "passive"))
      (node (ref "R60") (pin "2") (pinfunction "2_2") (pintype "passive"))
      (node (ref "R63") (pin "2") (pinfunction "2_2") (pintype "passive"))
      (node (ref "R64") (pin "2") (pinfunction "2_2") (pintype "passive"))
    )
    (net (code "6") (name "GND") (class "Default")
      (node (ref "C1") (pin "+") (pinfunction "+_+") (pintype "passive"))
      (node (ref "C10") (pin "2") (pinfunction "2_2") (pintype "passive"))
      (node (ref "C11") (pin "1") (pinfunction "1_1") (pintype "passive"))
      (node (ref "C12") (pin "2") (pinfunction "2_2") (pintype "passive"))
      (node (ref "C13") (pin "2") (pinfunction "2_2") (pintype "passive"))
      (node (ref "C14") (pin "2") (pinfunction "2_2") (pintype "passive"))
      (node (ref "C15") (pin "1") (pinfunction "1_1") (pintype "passive"))
      (node (ref "C16") (pin "2") (pinfunction "2_2") (pintype "passive"))
      (node (ref "C19") (pin "2") (pinfunction "2_2") (pintype "passive"))
      (node (ref "C2") (pin "-") (pinfunction "-_-") (pintype "passive"))
      (node (ref "C20") (pin "1") (pinfunction "1_1") (pintype "passive"))
      (node (ref "C21") (pin "-") (pinfunction "-_-") (pintype "passive"))
      (node (ref "C22") (pin "+") (pinfunction "+_+") (pintype "passive"))
      (node (ref "C23") (pin "1") (pinfunction "1_1") (pintype "passive"))
      (node (ref "C24") (pin "2") (pinfunction "2_2") (pintype "passive"))
      (node (ref "C27") (pin "2") (pinfunction "2_2") (pintype "passive"))
      (node (ref "C28") (pin "2") (pinfunction "2_2") (pintype "passive"))
      (node (ref "C29") (pin "2") (pinfunction "2_2") (pintype "passive"))
      (node (ref "C3") (pin "1") (pinfunction "1_1") (pintype "passive"))
      (node (ref "C30") (pin "2") (pinfunction "2_2") (pintype "passive"))
      (node (ref "C31") (pin "1") (pinfunction "1_1") (pintype "passive"))
      (node (ref "C32") (pin "2") (pinfunction "2_2") (pintype "passive"))
      (node (ref "C33") (pin "2") (pinfunction "2_2") (pintype "passive"))
      (node (ref "C34") (pin "2") (pinfunction "2_2") (pintype "passive"))
      (node (ref "C35") (pin "1") (pinfunction "1_1") (pintype "passive"))
      (node (ref "C36") (pin "2") (pinfunction "2_2") (pintype "passive"))
      (node (ref "C39") (pin "1") (pinfunction "1_1") (pintype "passive"))
      (node (ref "C4") (pin "2") (pinfunction "2_2") (pintype "passive"))
      (node (ref "C40") (pin "2") (pinfunction "2_2") (pintype "passive"))
      (node (ref "C7") (pin "2") (pinfunction "2_2") (pintype "passive"))
      (node (ref "C8") (pin "2") (pinfunction "2_2") (pintype "passive"))
      (node (ref "C9") (pin "2") (pinfunction "2_2") (pintype "passive"))
      (node (ref "D1") (pin "C") (pinfunction "C_C") (pintype "passive"))
      (node (ref "IC1") (pin "10") (pinfunction "+IN_10") (pintype "input"))
      (node (ref "IC1") (pin "12") (pinfunction "+IN_12") (pintype "input"))
      (node (ref "IC1") (pin "3") (pinfunction "+IN_3") (pintype "input"))
      (node (ref "IC1") (pin "5") (pinfunction "+IN_5") (pintype "input"))
      (node (ref "IC10") (pin "10") (pinfunction "+IN_10") (pintype "input"))
      (node (ref "IC10") (pin "12") (pinfunction "+IN_12") (pintype "input"))
      (node (ref "IC10") (pin "3") (pinfunction "+IN_3") (pintype "input"))
      (node (ref "IC10") (pin "5") (pinfunction "+IN_5") (pintype "input"))
      (node (ref "IC3") (pin "8") (pinfunction "GND_8") (pintype "power_in"))
      (node (ref "IC4") (pin "10") (pinfunction "+IN_10") (pintype "input"))
      (node (ref "IC4") (pin "12") (pinfunction "+IN_12") (pintype "input"))
      (node (ref "IC4") (pin "3") (pinfunction "+IN_3") (pintype "input"))
      (node (ref "IC4") (pin "5") (pinfunction "+IN_5") (pintype "input"))
      (node (ref "IC5") (pin "10") (pinfunction "+IN_10") (pintype "input"))
      (node (ref "IC5") (pin "12") (pinfunction "+IN_12") (pintype "input"))
      (node (ref "IC5") (pin "3") (pinfunction "+IN_3") (pintype "input"))
      (node (ref "IC5") (pin "5") (pinfunction "+IN_5") (pintype "input"))
      (node (ref "IC7") (pin "8") (pinfunction "GND_8") (pintype "power_in"))
      (node (ref "IC8") (pin "1") (pinfunction "C_1") (pintype "passive"))
      (node (ref "IC9") (pin "2") (pinfunction "A_2") (pintype "passive"))
      (node (ref "J1") (pin "P1") (pinfunction "1_P1") (pintype "passive"))
      (node (ref "J1") (pin "P2") (pinfunction "2_P2") (pintype "passive"))
      (node (ref "J10") (pin "P1") (pinfunction "1_P1") (pintype "passive"))
      (node (ref "J10") (pin "P2") (pinfunction "2_P2") (pintype "passive"))
      (node (ref "J11") (pin "P1") (pinfunction "1_P1") (pintype "passive"))
      (node (ref "J12") (pin "P1") (pinfunction "1_P1") (pintype "passive"))
      (node (ref "J2") (pin "P1") (pinfunction "1_P1") (pintype "passive"))
      (node (ref "J3") (pin "P1") (pinfunction "1_P1") (pintype "passive"))
      (node (ref "J4") (pin "P1") (pinfunction "1_P1") (pintype "passive"))
      (node (ref "J4") (pin "P2") (pinfunction "2_P2") (pintype "passive"))
      (node (ref "J5") (pin "P1") (pinfunction "1_P1") (pintype "passive"))
      (node (ref "J6") (pin "P1") (pinfunction "1_P1") (pintype "passive"))
      (node (ref "J7") (pin "P1") (pinfunction "1_P1") (pintype "passive"))
      (node (ref "J7") (pin "P2") (pinfunction "2_P2") (pintype "passive"))
      (node (ref "J8") (pin "P1") (pinfunction "1_P1") (pintype "passive"))
      (node (ref "J9") (pin "P1") (pinfunction "1_P1") (pintype "passive"))
      (node (ref "JP5") (pin "3") (pinfunction "3_3") (pintype "passive"))
      (node (ref "JP5") (pin "4") (pinfunction "4_4") (pintype "passive"))
      (node (ref "JP5") (pin "5") (pinfunction "5_5") (pintype "passive"))
      (node (ref "JP5") (pin "6") (pinfunction "6_6") (pintype "passive"))
      (node (ref "JP5") (pin "7") (pinfunction "7_7") (pintype "passive"))
      (node (ref "JP5") (pin "8") (pinfunction "8_8") (pintype "passive"))
      (node (ref "R15") (pin "1") (pinfunction "1_1") (pintype "passive"))
      (node (ref "R27") (pin "1") (pinfunction "1_1") (pintype "passive"))
      (node (ref "R29") (pin "P$3") (pinfunction "A_P$3") (pintype "passive"))
      (node (ref "R3") (pin "P$3") (pinfunction "A_P$3") (pintype "passive"))
      (node (ref "R35") (pin "1") (pinfunction "1_1") (pintype "passive"))
      (node (ref "R38") (pin "2") (pinfunction "2_2") (pintype "passive"))
      (node (ref "R42") (pin "P$3") (pinfunction "A_P$3") (pintype "passive"))
      (node (ref "R45") (pin "2") (pinfunction "2_2") (pintype "passive"))
      (node (ref "R47") (pin "1") (pinfunction "1_1") (pintype "passive"))
      (node (ref "R55") (pin "1") (pinfunction "1_1") (pintype "passive"))
      (node (ref "R6") (pin "2") (pinfunction "2_2") (pintype "passive"))
      (node (ref "R68") (pin "1") (pinfunction "1_1") (pintype "passive"))
      (node (ref "R70") (pin "P$3") (pinfunction "A_P$3") (pintype "passive"))
      (node (ref "R77") (pin "1") (pinfunction "1_1") (pintype "passive"))
      (node (ref "R78") (pin "2") (pinfunction "2_2") (pintype "passive"))
      (node (ref "R8") (pin "1") (pinfunction "1_1") (pintype "passive"))
    )
    (net (code "7") (name "Net-(C9-Pad1)") (class "Default")
      (node (ref "C9") (pin "1") (pinfunction "1_1") (pintype "passive"))
      (node (ref "R13") (pin "1") (pinfunction "1_1") (pintype "passive"))
    )
    (net (code "8") (name "Net-(C10-Pad1)") (class "Default")
      (node (ref "C10") (pin "1") (pinfunction "1_1") (pintype "passive"))
      (node (ref "R18") (pin "1") (pinfunction "1_1") (pintype "passive"))
    )
    (net (code "9") (name "Net-(C13-Pad1)") (class "Default")
      (node (ref "C13") (pin "1") (pinfunction "1_1") (pintype "passive"))
      (node (ref "R21") (pin "1") (pinfunction "1_1") (pintype "passive"))
    )
    (net (code "10") (name "Net-(C14-Pad1)") (class "Default")
      (node (ref "C14") (pin "1") (pinfunction "1_1") (pintype "passive"))
      (node (ref "R24") (pin "1") (pinfunction "1_1") (pintype "passive"))
    )
    (net (code "11") (name "Net-(C29-Pad1)") (class "Default")
      (node (ref "C29") (pin "1") (pinfunction "1_1") (pintype "passive"))
      (node (ref "R53") (pin "1") (pinfunction "1_1") (pintype "passive"))
    )
    (net (code "12") (name "Net-(C30-Pad1)") (class "Default")
      (node (ref "C30") (pin "1") (pinfunction "1_1") (pintype "passive"))
      (node (ref "R58") (pin "1") (pinfunction "1_1") (pintype "passive"))
    )
    (net (code "13") (name "Net-(C33-Pad1)") (class "Default")
      (node (ref "C33") (pin "1") (pinfunction "1_1") (pintype "passive"))
      (node (ref "R61") (pin "1") (pinfunction "1_1") (pintype "passive"))
    )
    (net (code "14") (name "Net-(C34-Pad1)") (class "Default")
      (node (ref "C34") (pin "1") (pinfunction "1_1") (pintype "passive"))
      (node (ref "R65") (pin "1") (pinfunction "1_1") (pintype "passive"))
    )
    (net (code "15") (name "Net-(D2-PadA)") (class "Default")
      (node (ref "D2") (pin "A") (pinfunction "A_A") (pintype "passive"))
      (node (ref "JP5") (pin "1") (pinfunction "1_1") (pintype "passive"))
      (node (ref "JP5") (pin "2") (pinfunction "2_2") (pintype "passive"))
    )
    (net (code "16") (name "Net-(D2-PadC)") (class "Default")
      (node (ref "D2") (pin "C") (pinfunction "C_C") (pintype "passive"))
      (node (ref "L2") (pin "2") (pinfunction "2_2") (pintype "passive"))
    )
    (net (code "17") (name "Net-(IC1A--IN)") (class "Default")
      (node (ref "C5") (pin "1") (pinfunction "1_1") (pintype "passive"))
      (node (ref "IC1") (pin "2") (pinfunction "-IN_2") (pintype "input"))
      (node (ref "IC3") (pin "4") (pinfunction "OUT_4") (pintype "output"))
      (node (ref "R19") (pin "1") (pinfunction "1_1") (pintype "passive"))
      (node (ref "R3") (pin "P$1") (pinfunction "E_P$1") (pintype "passive"))
    )
    (net (code "18") (name "Net-(IC1A-OUT)") (class "Default")
      (node (ref "C5") (pin "2") (pinfunction "2_2") (pintype "passive"))
      (node (ref "IC1") (pin "1") (pinfunction "OUT_1") (pintype "output"))
      (node (ref "IC3") (pin "14") (pinfunction "CTRL_14") (pintype "input"))
      (node (ref "R1") (pin "P$1") (pinfunction "E_P$1") (pintype "passive"))
    )
    (net (code "19") (name "Net-(IC1B--IN)") (class "Default")
      (node (ref "C41") (pin "1") (pinfunction "1_1") (pintype "passive"))
      (node (ref "IC1") (pin "6") (pinfunction "-IN_6") (pintype "input"))
      (node (ref "IC3") (pin "13") (pinfunction "OUT_13") (pintype "output"))
      (node (ref "R7") (pin "2") (pinfunction "2_2") (pintype "passive"))
    )
    (net (code "20") (name "Net-(IC1B-OUT)") (class "Default")
      (node (ref "C41") (pin "2") (pinfunction "2_2") (pintype "passive"))
      (node (ref "IC1") (pin "7") (pinfunction "OUT_7") (pintype "output"))
      (node (ref "R7") (pin "1") (pinfunction "1_1") (pintype "passive"))
      (node (ref "R9") (pin "2") (pinfunction "2_2") (pintype "passive"))
    )
    (net (code "21") (name "Net-(IC1C--IN)") (class "Default")
      (node (ref "C6") (pin "1") (pinfunction "1_1") (pintype "passive"))
      (node (ref "IC1") (pin "9") (pinfunction "-IN_9") (pintype "input"))
      (node (ref "R10") (pin "2") (pinfunction "2_2") (pintype "passive"))
      (node (ref "R9") (pin "1") (pinfunction "1_1") (pintype "passive"))
    )
    (net (code "22") (name "Net-(IC1C-OUT)") (class "Default")
      (node (ref "C6") (pin "2") (pinfunction "2_2") (pintype "passive"))
      (node (ref "IC1") (pin "8") (pinfunction "OUT_8") (pintype "output"))
      (node (ref "R10") (pin "1") (pinfunction "1_1") (pintype "passive"))
      (node (ref "R12") (pin "1") (pinfunction "1_1") (pintype "passive"))
      (node (ref "R2") (pin "2") (pinfunction "2_2") (pintype "passive"))
    )
    (net (code "23") (name "Net-(IC1D--IN)") (class "Default")
      (node (ref "IC1") (pin "13") (pinfunction "-IN_13") (pintype "input"))
      (node (ref "R4") (pin "2") (pinfunction "2_2") (pintype "passive"))
      (node (ref "R5") (pin "1") (pinfunction "1_1") (pintype "passive"))
    )
    (net (code "24") (name "Net-(IC2A-+IN)") (class "Default")
      (node (ref "IC2") (pin "3") (pinfunction "+IN_3") (pintype "input"))
      (node (ref "R12") (pin "2") (pinfunction "2_2") (pintype "passive"))
      (node (ref "R15") (pin "2") (pinfunction "2_2") (pintype "passive"))
    )
    (net (code "25") (name "Net-(IC2A--IN)") (class "Default")
      (node (ref "IC2") (pin "2") (pinfunction "-IN_2") (pintype "input"))
      (node (ref "LED1") (pin "A") (pinfunction "A_A") (pintype "passive"))
      (node (ref "R6") (pin "1") (pinfunction "1_1") (pintype "passive"))
    )
    (net (code "26") (name "Net-(IC2A-OUT)") (class "Default")
      (node (ref "IC2") (pin "1") (pinfunction "OUT_1") (pintype "output"))
      (node (ref "LED1") (pin "K") (pinfunction "C_K") (pintype "passive"))
    )
    (net (code "27") (name "Net-(IC2B-+IN)") (class "Default")
      (node (ref "IC2") (pin "5") (pinfunction "+IN_5") (pintype "input"))
      (node (ref "R26") (pin "2") (pinfunction "2_2") (pintype "passive"))
      (node (ref "R27") (pin "2") (pinfunction "2_2") (pintype "passive"))
    )
    (net (code "28") (name "Net-(IC2B--IN)") (class "Default")
      (node (ref "IC2") (pin "6") (pinfunction "-IN_6") (pintype "input"))
      (node (ref "LED2") (pin "A") (pinfunction "A_A") (pintype "passive"))
      (node (ref "R38") (pin "1") (pinfunction "1_1") (pintype "passive"))
    )
    (net (code "29") (name "Net-(IC2B-OUT)") (class "Default")
      (node (ref "IC2") (pin "7") (pinfunction "OUT_7") (pintype "output"))
      (node (ref "LED2") (pin "K") (pinfunction "C_K") (pintype "passive"))
    )
    (net (code "30") (name "Net-(IC3A-CTRL)") (class "Default")
      (node (ref "IC3") (pin "3") (pinfunction "CTRL_3") (pintype "input"))
      (node (ref "R1") (pin "P$2") (pinfunction "S_P$2") (pintype "passive"))
    )
    (net (code "31") (name "Net-(IC3A-IN)") (class "Default")
      (node (ref "IC3") (pin "2") (pinfunction "IN_2") (pintype "input"))
      (node (ref "R13") (pin "2") (pinfunction "2_2") (pintype "passive"))
      (node (ref "R17") (pin "1") (pinfunction "1_1") (pintype "passive"))
    )
    (net (code "32") (name "Net-(IC3B-CTRL)") (class "Default")
      (node (ref "IC3") (pin "6") (pinfunction "CTRL_6") (pintype "input"))
      (node (ref "R28") (pin "P$2") (pinfunction "S_P$2") (pintype "passive"))
    )
    (net (code "33") (name "Net-(IC3B-IN)") (class "Default")
      (node (ref "IC3") (pin "7") (pinfunction "IN_7") (pintype "input"))
      (node (ref "R23") (pin "1") (pinfunction "1_1") (pintype "passive"))
      (node (ref "R24") (pin "2") (pinfunction "2_2") (pintype "passive"))
    )
    (net (code "34") (name "Net-(IC3B-OUT)") (class "Default")
      (node (ref "C18") (pin "1") (pinfunction "1_1") (pintype "passive"))
      (node (ref "IC3") (pin "5") (pinfunction "OUT_5") (pintype "output"))
      (node (ref "IC4") (pin "6") (pinfunction "-IN_6") (pintype "input"))
      (node (ref "R20") (pin "1") (pinfunction "1_1") (pintype "passive"))
      (node (ref "R29") (pin "P$1") (pinfunction "E_P$1") (pintype "passive"))
    )
    (net (code "35") (name "Net-(IC3C-CTRL)") (class "Default")
      (node (ref "C18") (pin "2") (pinfunction "2_2") (pintype "passive"))
      (node (ref "IC3") (pin "11") (pinfunction "CTRL_11") (pintype "input"))
      (node (ref "IC4") (pin "7") (pinfunction "OUT_7") (pintype "output"))
      (node (ref "R28") (pin "P$1") (pinfunction "E_P$1") (pintype "passive"))
    )
    (net (code "36") (name "Net-(IC3C-IN)") (class "Default")
      (node (ref "IC3") (pin "10") (pinfunction "IN_10") (pintype "input"))
      (node (ref "R21") (pin "2") (pinfunction "2_2") (pintype "passive"))
      (node (ref "R25") (pin "1") (pinfunction "1_1") (pintype "passive"))
    )
    (net (code "37") (name "Net-(IC3C-OUT)") (class "Default")
      (node (ref "C42") (pin "1") (pinfunction "1_1") (pintype "passive"))
      (node (ref "IC3") (pin "12") (pinfunction "OUT_12") (pintype "output"))
      (node (ref "IC4") (pin "2") (pinfunction "-IN_2") (pintype "input"))
      (node (ref "R33") (pin "2") (pinfunction "2_2") (pintype "passive"))
    )
    (net (code "38") (name "Net-(IC3D-IN)") (class "Default")
      (node (ref "IC3") (pin "15") (pinfunction "IN_15") (pintype "input"))
      (node (ref "R14") (pin "1") (pinfunction "1_1") (pintype "passive"))
      (node (ref "R18") (pin "2") (pinfunction "2_2") (pintype "passive"))
    )
    (net (code "39") (name "Net-(IC4A-OUT)") (class "Default")
      (node (ref "C42") (pin "2") (pinfunction "2_2") (pintype "passive"))
      (node (ref "IC4") (pin "1") (pinfunction "OUT_1") (pintype "output"))
      (node (ref "R32") (pin "2") (pinfunction "2_2") (pintype "passive"))
      (node (ref "R33") (pin "1") (pinfunction "1_1") (pintype "passive"))
    )
    (net (code "40") (name "Net-(IC4C--IN)") (class "Default")
      (node (ref "IC4") (pin "9") (pinfunction "-IN_9") (pintype "input"))
      (node (ref "R34") (pin "1") (pinfunction "1_1") (pintype "passive"))
      (node (ref "R36") (pin "2") (pinfunction "2_2") (pintype "passive"))
    )
    (net (code "41") (name "Net-(IC4D--IN)") (class "Default")
      (node (ref "C17") (pin "1") (pinfunction "1_1") (pintype "passive"))
      (node (ref "IC4") (pin "13") (pinfunction "-IN_13") (pintype "input"))
      (node (ref "R30") (pin "1") (pinfunction "1_1") (pintype "passive"))
      (node (ref "R31") (pin "2") (pinfunction "2_2") (pintype "passive"))
      (node (ref "R32") (pin "1") (pinfunction "1_1") (pintype "passive"))
    )
    (net (code "42") (name "Net-(IC4D-OUT)") (class "Default")
      (node (ref "C17") (pin "2") (pinfunction "2_2") (pintype "passive"))
      (node (ref "IC4") (pin "14") (pinfunction "OUT_14") (pintype "output"))
      (node (ref "R22") (pin "2") (pinfunction "2_2") (pintype "passive"))
      (node (ref "R26") (pin "1") (pinfunction "1_1") (pintype "passive"))
      (node (ref "R31") (pin "1") (pinfunction "1_1") (pintype "passive"))
    )
    (net (code "43") (name "Net-(IC5A--IN)") (class "Default")
      (node (ref "C25") (pin "1") (pinfunction "1_1") (pintype "passive"))
      (node (ref "IC5") (pin "2") (pinfunction "-IN_2") (pintype "input"))
      (node (ref "IC7") (pin "4") (pinfunction "OUT_4") (pintype "output"))
      (node (ref "R42") (pin "P$1") (pinfunction "E_P$1") (pintype "passive"))
      (node (ref "R59") (pin "1") (pinfunction "1_1") (pintype "passive"))
    )
    (net (code "44") (name "Net-(IC5A-OUT)") (class "Default")
      (node (ref "C25") (pin "2") (pinfunction "2_2") (pintype "passive"))
      (node (ref "IC5") (pin "1") (pinfunction "OUT_1") (pintype "output"))
      (node (ref "IC7") (pin "14") (pinfunction "CTRL_14") (pintype "input"))
      (node (ref "R40") (pin "P$1") (pinfunction "E_P$1") (pintype "passive"))
    )
    (net (code "45") (name "Net-(IC5B--IN)") (class "Default")
      (node (ref "C43") (pin "1") (pinfunction "1_1") (pintype "passive"))
      (node (ref "IC5") (pin "6") (pinfunction "-IN_6") (pintype "input"))
      (node (ref "IC7") (pin "13") (pinfunction "OUT_13") (pintype "output"))
      (node (ref "R46") (pin "2") (pinfunction "2_2") (pintype "passive"))
    )
    (net (code "46") (name "Net-(IC5B-OUT)") (class "Default")
      (node (ref "C43") (pin "2") (pinfunction "2_2") (pintype "passive"))
      (node (ref "IC5") (pin "7") (pinfunction "OUT_7") (pintype "output"))
      (node (ref "R46") (pin "1") (pinfunction "1_1") (pintype "passive"))
      (node (ref "R49") (pin "2") (pinfunction "2_2") (pintype "passive"))
    )
    (net (code "47") (name "Net-(IC5C--IN)") (class "Default")
      (node (ref "C26") (pin "1") (pinfunction "1_1") (pintype "passive"))
      (node (ref "IC5") (pin "9") (pinfunction "-IN_9") (pintype "input"))
      (node (ref "R48") (pin "1") (pinfunction "1_1") (pintype "passive"))
      (node (ref "R49") (pin "1") (pinfunction "1_1") (pintype "passive"))
      (node (ref "R50") (pin "2") (pinfunction "2_2") (pintype "passive"))
    )
    (net (code "48") (name "Net-(IC5C-OUT)") (class "Default")
      (node (ref "C26") (pin "2") (pinfunction "2_2") (pintype "passive"))
      (node (ref "IC5") (pin "8") (pinfunction "OUT_8") (pintype "output"))
      (node (ref "R41") (pin "2") (pinfunction "2_2") (pintype "passive"))
      (node (ref "R50") (pin "1") (pinfunction "1_1") (pintype "passive"))
      (node (ref "R52") (pin "1") (pinfunction "1_1") (pintype "passive"))
    )
    (net (code "49") (name "Net-(IC5D--IN)") (class "Default")
      (node (ref "IC5") (pin "13") (pinfunction "-IN_13") (pintype "input"))
      (node (ref "R43") (pin "2") (pinfunction "2_2") (pintype "passive"))
      (node (ref "R44") (pin "1") (pinfunction "1_1") (pintype "passive"))
    )
    (net (code "50") (name "Net-(IC6A-+IN)") (class "Default")
      (node (ref "IC6") (pin "3") (pinfunction "+IN_3") (pintype "input"))
      (node (ref "R52") (pin "2") (pinfunction "2_2") (pintype "passive"))
      (node (ref "R55") (pin "2") (pinfunction "2_2") (pintype "passive"))
    )
    (net (code "51") (name "Net-(IC6A--IN)") (class "Default")
      (node (ref "IC6") (pin "2") (pinfunction "-IN_2") (pintype "input"))
      (node (ref "LED3") (pin "A") (pinfunction "A_A") (pintype "passive"))
      (node (ref "R45") (pin "1") (pinfunction "1_1") (pintype "passive"))
    )
    (net (code "52") (name "Net-(IC6A-OUT)") (class "Default")
      (node (ref "IC6") (pin "1") (pinfunction "OUT_1") (pintype "output"))
      (node (ref "LED3") (pin "K") (pinfunction "C_K") (pintype "passive"))
    )
    (net (code "53") (name "Net-(IC6B-+IN)") (class "Default")
      (node (ref "IC6") (pin "5") (pinfunction "+IN_5") (pintype "input"))
      (node (ref "R67") (pin "2") (pinfunction "2_2") (pintype "passive"))
      (node (ref "R68") (pin "2") (pinfunction "2_2") (pintype "passive"))
    )
    (net (code "54") (name "Net-(IC6B--IN)") (class "Default")
      (node (ref "IC6") (pin "6") (pinfunction "-IN_6") (pintype "input"))
      (node (ref "LED4") (pin "A") (pinfunction "A_A") (pintype "passive"))
      (node (ref "R78") (pin "1") (pinfunction "1_1") (pintype "passive"))
    )
    (net (code "55") (name "Net-(IC6B-OUT)") (class "Default")
      (node (ref "IC6") (pin "7") (pinfunction "OUT_7") (pintype "output"))
      (node (ref "LED4") (pin "K") (pinfunction "C_K") (pintype "passive"))
    )
    (net (code "56") (name "Net-(IC7A-CTRL)") (class "Default")
      (node (ref "IC7") (pin "3") (pinfunction "CTRL_3") (pintype "input"))
      (node (ref "R40") (pin "P$2") (pinfunction "S_P$2") (pintype "passive"))
    )
    (net (code "57") (name "Net-(IC7A-IN)") (class "Default")
      (node (ref "IC7") (pin "2") (pinfunction "IN_2") (pintype "input"))
      (node (ref "R53") (pin "2") (pinfunction "2_2") (pintype "passive"))
      (node (ref "R57") (pin "1") (pinfunction "1_1") (pintype "passive"))
    )
    (net (code "58") (name "Net-(IC7B-CTRL)") (class "Default")
      (node (ref "IC7") (pin "6") (pinfunction "CTRL_6") (pintype "input"))
      (node (ref "R69") (pin "P$2") (pinfunction "S_P$2") (pintype "passive"))
    )
    (net (code "59") (name "Net-(IC7B-IN)") (class "Default")
      (node (ref "IC7") (pin "7") (pinfunction "IN_7") (pintype "input"))
      (node (ref "R63") (pin "1") (pinfunction "1_1") (pintype "passive"))
      (node (ref "R65") (pin "2") (pinfunction "2_2") (pintype "passive"))
    )
    (net (code "60") (name "Net-(IC7C-IN)") (class "Default")
      (node (ref "IC7") (pin "10") (pinfunction "IN_10") (pintype "input"))
      (node (ref "R61") (pin "2") (pinfunction "2_2") (pintype "passive"))
      (node (ref "R66") (pin "1") (pinfunction "1_1") (pintype "passive"))
    )
    (net (code "61") (name "Net-(IC7D-IN)") (class "Default")
      (node (ref "IC7") (pin "15") (pinfunction "IN_15") (pintype "input"))
      (node (ref "R54") (pin "1") (pinfunction "1_1") (pintype "passive"))
      (node (ref "R58") (pin "2") (pinfunction "2_2") (pintype "passive"))
    )
    (net (code "62") (name "Net-(IC10A--IN)") (class "Default")
      (node (ref "C44") (pin "1") (pinfunction "1_1") (pintype "passive"))
      (node (ref "IC10") (pin "2") (pinfunction "-IN_2") (pintype "input"))
      (node (ref "IC7") (pin "12") (pinfunction "OUT_12") (pintype "output"))
      (node (ref "R76") (pin "2") (pinfunction "2_2") (pintype "passive"))
    )
    (net (code "63") (name "Net-(IC10A-OUT)") (class "Default")
      (node (ref "C44") (pin "2") (pinfunction "2_2") (pintype "passive"))
      (node (ref "IC10") (pin "1") (pinfunction "OUT_1") (pintype "output"))
      (node (ref "R75") (pin "2") (pinfunction "2_2") (pintype "passive"))
      (node (ref "R76") (pin "1") (pinfunction "1_1") (pintype "passive"))
    )
    (net (code "64") (name "Net-(IC10B--IN)") (class "Default")
      (node (ref "C38") (pin "1") (pinfunction "1_1") (pintype "passive"))
      (node (ref "IC10") (pin "6") (pinfunction "-IN_6") (pintype "input"))
      (node (ref "IC7") (pin "5") (pinfunction "OUT_5") (pintype "output"))
      (node (ref "R60") (pin "1") (pinfunction "1_1") (pintype "passive"))
      (node (ref "R70") (pin "P$1") (pinfunction "E_P$1") (pintype "passive"))
    )
    (net (code "65") (name "Net-(IC10B-OUT)") (class "Default")
      (node (ref "C38") (pin "2") (pinfunction "2_2") (pintype "passive"))
      (node (ref "IC10") (pin "7") (pinfunction "OUT_7") (pintype "output"))
      (node (ref "IC7") (pin "11") (pinfunction "CTRL_11") (pintype "input"))
      (node (ref "R69") (pin "P$1") (pinfunction "E_P$1") (pintype "passive"))
    )
    (net (code "66") (name "Net-(IC10C--IN)") (class "Default")
      (node (ref "IC10") (pin "8") (pinfunction "OUT_8") (pintype "output"))
      (node (ref "IC10") (pin "9") (pinfunction "-IN_9") (pintype "input"))
    )
    (net (code "67") (name "Net-(IC10D--IN)") (class "Default")
      (node (ref "C37") (pin "1") (pinfunction "1_1") (pintype "passive"))
      (node (ref "IC10") (pin "13") (pinfunction "-IN_13") (pintype "input"))
      (node (ref "R71") (pin "1") (pinfunction "1_1") (pintype "passive"))
      (node (ref "R73") (pin "2") (pinfunction "2_2") (pintype "passive"))
      (node (ref "R75") (pin "1") (pinfunction "1_1") (pintype "passive"))
    )
    (net (code "68") (name "Net-(IC10D-OUT)") (class "Default")
      (node (ref "C37") (pin "2") (pinfunction "2_2") (pintype "passive"))
      (node (ref "IC10") (pin "14") (pinfunction "OUT_14") (pintype "output"))
      (node (ref "R62") (pin "2") (pinfunction "2_2") (pintype "passive"))
      (node (ref "R67") (pin "1") (pinfunction "1_1") (pintype "passive"))
      (node (ref "R73") (pin "1") (pinfunction "1_1") (pintype "passive"))
    )
    (net (code "69") (name "Net-(J1-3)") (class "Default")
      (node (ref "J1") (pin "P3") (pinfunction "3_P3") (pintype "passive"))
      (node (ref "R14") (pin "2") (pinfunction "2_2") (pintype "passive"))
    )
    (net (code "70") (name "Net-(J2-2)") (class "Default")
      (node (ref "J2") (pin "P2") (pinfunction "2_P2") (pintype "passive"))
      (node (ref "R5") (pin "2") (pinfunction "2_2") (pintype "passive"))
    )
    (net (code "71") (name "Net-(J2-3)") (class "Default")
      (node (ref "J2") (pin "P3") (pinfunction "3_P3") (pintype "passive"))
      (node (ref "R2") (pin "1") (pinfunction "1_1") (pintype "passive"))
    )
    (net (code "72") (name "Net-(J3-2)") (class "Default")
      (node (ref "J3") (pin "P2") (pinfunction "2_P2") (pintype "passive"))
      (node (ref "R16") (pin "1") (pinfunction "1_1") (pintype "passive"))
    )
    (net (code "73") (name "Net-(J3-3)") (class "Default")
      (node (ref "J3") (pin "P3") (pinfunction "3_P3") (pintype "passive"))
      (node (ref "R11") (pin "2") (pinfunction "2_2") (pintype "passive"))
    )
    (net (code "74") (name "Net-(J4-3)") (class "Default")
      (node (ref "J4") (pin "P3") (pinfunction "3_P3") (pintype "passive"))
      (node (ref "R25") (pin "2") (pinfunction "2_2") (pintype "passive"))
    )
    (net (code "75") (name "Net-(J5-2)") (class "Default")
      (node (ref "J5") (pin "P2") (pinfunction "2_P2") (pintype "passive"))
      (node (ref "R34") (pin "2") (pinfunction "2_2") (pintype "passive"))
    )
    (net (code "76") (name "Net-(J5-3)") (class "Default")
      (node (ref "J5") (pin "P3") (pinfunction "3_P3") (pintype "passive"))
      (node (ref "R22") (pin "1") (pinfunction "1_1") (pintype "passive"))
    )
    (net (code "77") (name "Net-(J6-2)") (class "Default")
      (node (ref "J6") (pin "P2") (pinfunction "2_P2") (pintype "passive"))
      (node (ref "R39") (pin "1") (pinfunction "1_1") (pintype "passive"))
    )
    (net (code "78") (name "Net-(J6-3)") (class "Default")
      (node (ref "J6") (pin "P3") (pinfunction "3_P3") (pintype "passive"))
      (node (ref "R37") (pin "2") (pinfunction "2_2") (pintype "passive"))
    )
    (net (code "79") (name "Net-(J7-3)") (class "Default")
      (node (ref "J7") (pin "P3") (pinfunction "3_P3") (pintype "passive"))
      (node (ref "R54") (pin "2") (pinfunction "2_2") (pintype "passive"))
    )
    (net (code "80") (name "Net-(J8-2)") (class "Default")
      (node (ref "J8") (pin "P2") (pinfunction "2_P2") (pintype "passive"))
      (node (ref "R44") (pin "2") (pinfunction "2_2") (pintype "passive"))
    )
    (net (code "81") (name "Net-(J8-3)") (class "Default")
      (node (ref "J8") (pin "P3") (pinfunction "3_P3") (pintype "passive"))
      (node (ref "R41") (pin "1") (pinfunction "1_1") (pintype "passive"))
    )
    (net (code "82") (name "Net-(J9-2)") (class "Default")
      (node (ref "J9") (pin "P2") (pinfunction "2_P2") (pintype "passive"))
      (node (ref "R56") (pin "1") (pinfunction "1_1") (pintype "passive"))
    )
    (net (code "83") (name "Net-(J9-3)") (class "Default")
      (node (ref "J9") (pin "P3") (pinfunction "3_P3") (pintype "passive"))
      (node (ref "R51") (pin "2") (pinfunction "2_2") (pintype "passive"))
    )
    (net (code "84") (name "Net-(J10-3)") (class "Default")
      (node (ref "J10") (pin "P3") (pinfunction "3_P3") (pintype "passive"))
      (node (ref "R66") (pin "2") (pinfunction "2_2") (pintype "passive"))
    )
    (net (code "85") (name "Net-(J11-3)") (class "Default")
      (node (ref "J11") (pin "P3") (pinfunction "3_P3") (pintype "passive"))
      (node (ref "R62") (pin "1") (pinfunction "1_1") (pintype "passive"))
    )
    (net (code "86") (name "Net-(J12-2)") (class "Default")
      (node (ref "J12") (pin "P2") (pinfunction "2_P2") (pintype "passive"))
      (node (ref "R72") (pin "1") (pinfunction "1_1") (pintype "passive"))
    )
    (net (code "87") (name "Net-(J12-3)") (class "Default")
      (node (ref "J12") (pin "P3") (pinfunction "3_P3") (pintype "passive"))
      (node (ref "R79") (pin "2") (pinfunction "2_2") (pintype "passive"))
    )
    (net (code "88") (name "Net-(JP5-Pad10)") (class "Default")
      (node (ref "JP5") (pin "10") (pinfunction "10_10") (pintype "passive"))
      (node (ref "JP5") (pin "9") (pinfunction "9_9") (pintype "passive"))
      (node (ref "P1") (pin "2") (pinfunction "2_2") (pintype "bidirectional"))
    )
    (net (code "89") (name "Net-(L1-Pad2)") (class "Default")
      (node (ref "L1") (pin "2") (pinfunction "2_2") (pintype "passive"))
      (node (ref "P1") (pin "1") (pinfunction "1_1") (pintype "bidirectional"))
    )
    (net (code "90") (name "Net-(R1-A)") (class "Default")
      (node (ref "R1") (pin "P$3") (pinfunction "A_P$3") (pintype "passive"))
      (node (ref "R8") (pin "2") (pinfunction "2_2") (pintype "passive"))
    )
    (net (code "91") (name "Net-(R3-S)") (class "Default")
      (node (ref "R11") (pin "1") (pinfunction "1_1") (pintype "passive"))
      (node (ref "R3") (pin "P$2") (pinfunction "S_P$2") (pintype "passive"))
    )
    (net (code "92") (name "Net-(R28-A)") (class "Default")
      (node (ref "R28") (pin "P$3") (pinfunction "A_P$3") (pintype "passive"))
      (node (ref "R35") (pin "2") (pinfunction "2_2") (pintype "passive"))
    )
    (net (code "93") (name "Net-(R29-S)") (class "Default")
      (node (ref "R29") (pin "P$2") (pinfunction "S_P$2") (pintype "passive"))
      (node (ref "R37") (pin "1") (pinfunction "1_1") (pintype "passive"))
    )
    (net (code "94") (name "Net-(R40-A)") (class "Default")
      (node (ref "R40") (pin "P$3") (pinfunction "A_P$3") (pintype "passive"))
      (node (ref "R47") (pin "2") (pinfunction "2_2") (pintype "passive"))
    )
    (net (code "95") (name "Net-(R42-S)") (class "Default")
      (node (ref "R42") (pin "P$2") (pinfunction "S_P$2") (pintype "passive"))
      (node (ref "R51") (pin "1") (pinfunction "1_1") (pintype "passive"))
    )
    (net (code "96") (name "Net-(R69-A)") (class "Default")
      (node (ref "R69") (pin "P$3") (pinfunction "A_P$3") (pintype "passive"))
      (node (ref "R77") (pin "2") (pinfunction "2_2") (pintype "passive"))
    )
    (net (code "97") (name "Net-(R70-S)") (class "Default")
      (node (ref "R70") (pin "P$2") (pinfunction "S_P$2") (pintype "passive"))
      (node (ref "R79") (pin "1") (pinfunction "1_1") (pintype "passive"))
    )
    (net (code "98") (name "VCC") (class "Default")
      (node (ref "C19") (pin "1") (pinfunction "1_1") (pintype "passive"))
      (node (ref "C2") (pin "+") (pinfunction "+_+") (pintype "passive"))
      (node (ref "C21") (pin "+") (pinfunction "+_+") (pintype "passive"))
      (node (ref "C24") (pin "1") (pinfunction "1_1") (pintype "passive"))
      (node (ref "C27") (pin "1") (pinfunction "1_1") (pintype "passive"))
      (node (ref "C28") (pin "1") (pinfunction "1_1") (pintype "passive"))
      (node (ref "C4") (pin "1") (pinfunction "1_1") (pintype "passive"))
      (node (ref "C40") (pin "1") (pinfunction "1_1") (pintype "passive"))
      (node (ref "C7") (pin "1") (pinfunction "1_1") (pintype "passive"))
      (node (ref "C8") (pin "1") (pinfunction "1_1") (pintype "passive"))
      (node (ref "IC1") (pin "4") (pinfunction "V+_4") (pintype "power_in"))
      (node (ref "IC10") (pin "4") (pinfunction "V+_4") (pintype "power_in"))
      (node (ref "IC2") (pin "8") (pinfunction "V+_8") (pintype "power_in"))
      (node (ref "IC3") (pin "16") (pinfunction "V+_16") (pintype "power_in"))
      (node (ref "IC4") (pin "4") (pinfunction "V+_4") (pintype "power_in"))
      (node (ref "IC5") (pin "4") (pinfunction "V+_4") (pintype "power_in"))
      (node (ref "IC6") (pin "8") (pinfunction "V+_8") (pintype "power_in"))
      (node (ref "IC7") (pin "16") (pinfunction "V+_16") (pintype "power_in"))
      (node (ref "L2") (pin "1") (pinfunction "1_1") (pintype "passive"))
      (node (ref "R74") (pin "1") (pinfunction "1_1") (pintype "passive"))
    )
    (net (code "99") (name "VEE") (class "Default")
      (node (ref "C1") (pin "-") (pinfunction "-_-") (pintype "passive"))
      (node (ref "C11") (pin "2") (pinfunction "2_2") (pintype "passive"))
      (node (ref "C15") (pin "2") (pinfunction "2_2") (pintype "passive"))
      (node (ref "C20") (pin "2") (pinfunction "2_2") (pintype "passive"))
      (node (ref "C22") (pin "-") (pinfunction "-_-") (pintype "passive"))
      (node (ref "C23") (pin "2") (pinfunction "2_2") (pintype "passive"))
      (node (ref "C3") (pin "2") (pinfunction "2_2") (pintype "passive"))
      (node (ref "C31") (pin "2") (pinfunction "2_2") (pintype "passive"))
      (node (ref "C35") (pin "2") (pinfunction "2_2") (pintype "passive"))
      (node (ref "C39") (pin "2") (pinfunction "2_2") (pintype "passive"))
      (node (ref "D1") (pin "A") (pinfunction "A_A") (pintype "passive"))
      (node (ref "IC1") (pin "11") (pinfunction "V-_11") (pintype "power_in"))
      (node (ref "IC10") (pin "11") (pinfunction "V-_11") (pintype "power_in"))
      (node (ref "IC2") (pin "4") (pinfunction "V-_4") (pintype "power_in"))
      (node (ref "IC3") (pin "9") (pinfunction "V-_9") (pintype "power_in"))
      (node (ref "IC4") (pin "11") (pinfunction "V-_11") (pintype "power_in"))
      (node (ref "IC5") (pin "11") (pinfunction "V-_11") (pintype "power_in"))
      (node (ref "IC6") (pin "4") (pinfunction "V-_4") (pintype "power_in"))
      (node (ref "IC7") (pin "9") (pinfunction "V-_9") (pintype "power_in"))
      (node (ref "L1") (pin "1") (pinfunction "1_1") (pintype "passive"))
      (node (ref "R64") (pin "1") (pinfunction "1_1") (pintype "passive"))
    )
    (net (code "100") (name "unconnected-(IC3E-MODE-Pad1)") (class "Default")
      (node (ref "IC3") (pin "1") (pinfunction "MODE_1") (pintype "input"))
    )
    (net (code "101") (name "unconnected-(IC7E-MODE-Pad1)") (class "Default")
      (node (ref "IC7") (pin "1") (pinfunction "MODE_1") (pintype "input"))
    )
    (net (code "102") (name "unconnected-(J11-2-PadP2)") (class "Default")
      (node (ref "J11") (pin "P2") (pinfunction "2_P2") (pintype "passive"))
    )
  )
)
